# SBC_65C02_IRQ_BigBoard_v10-2-1.net
KiCad netlist of a schematic drawn in EAGLE
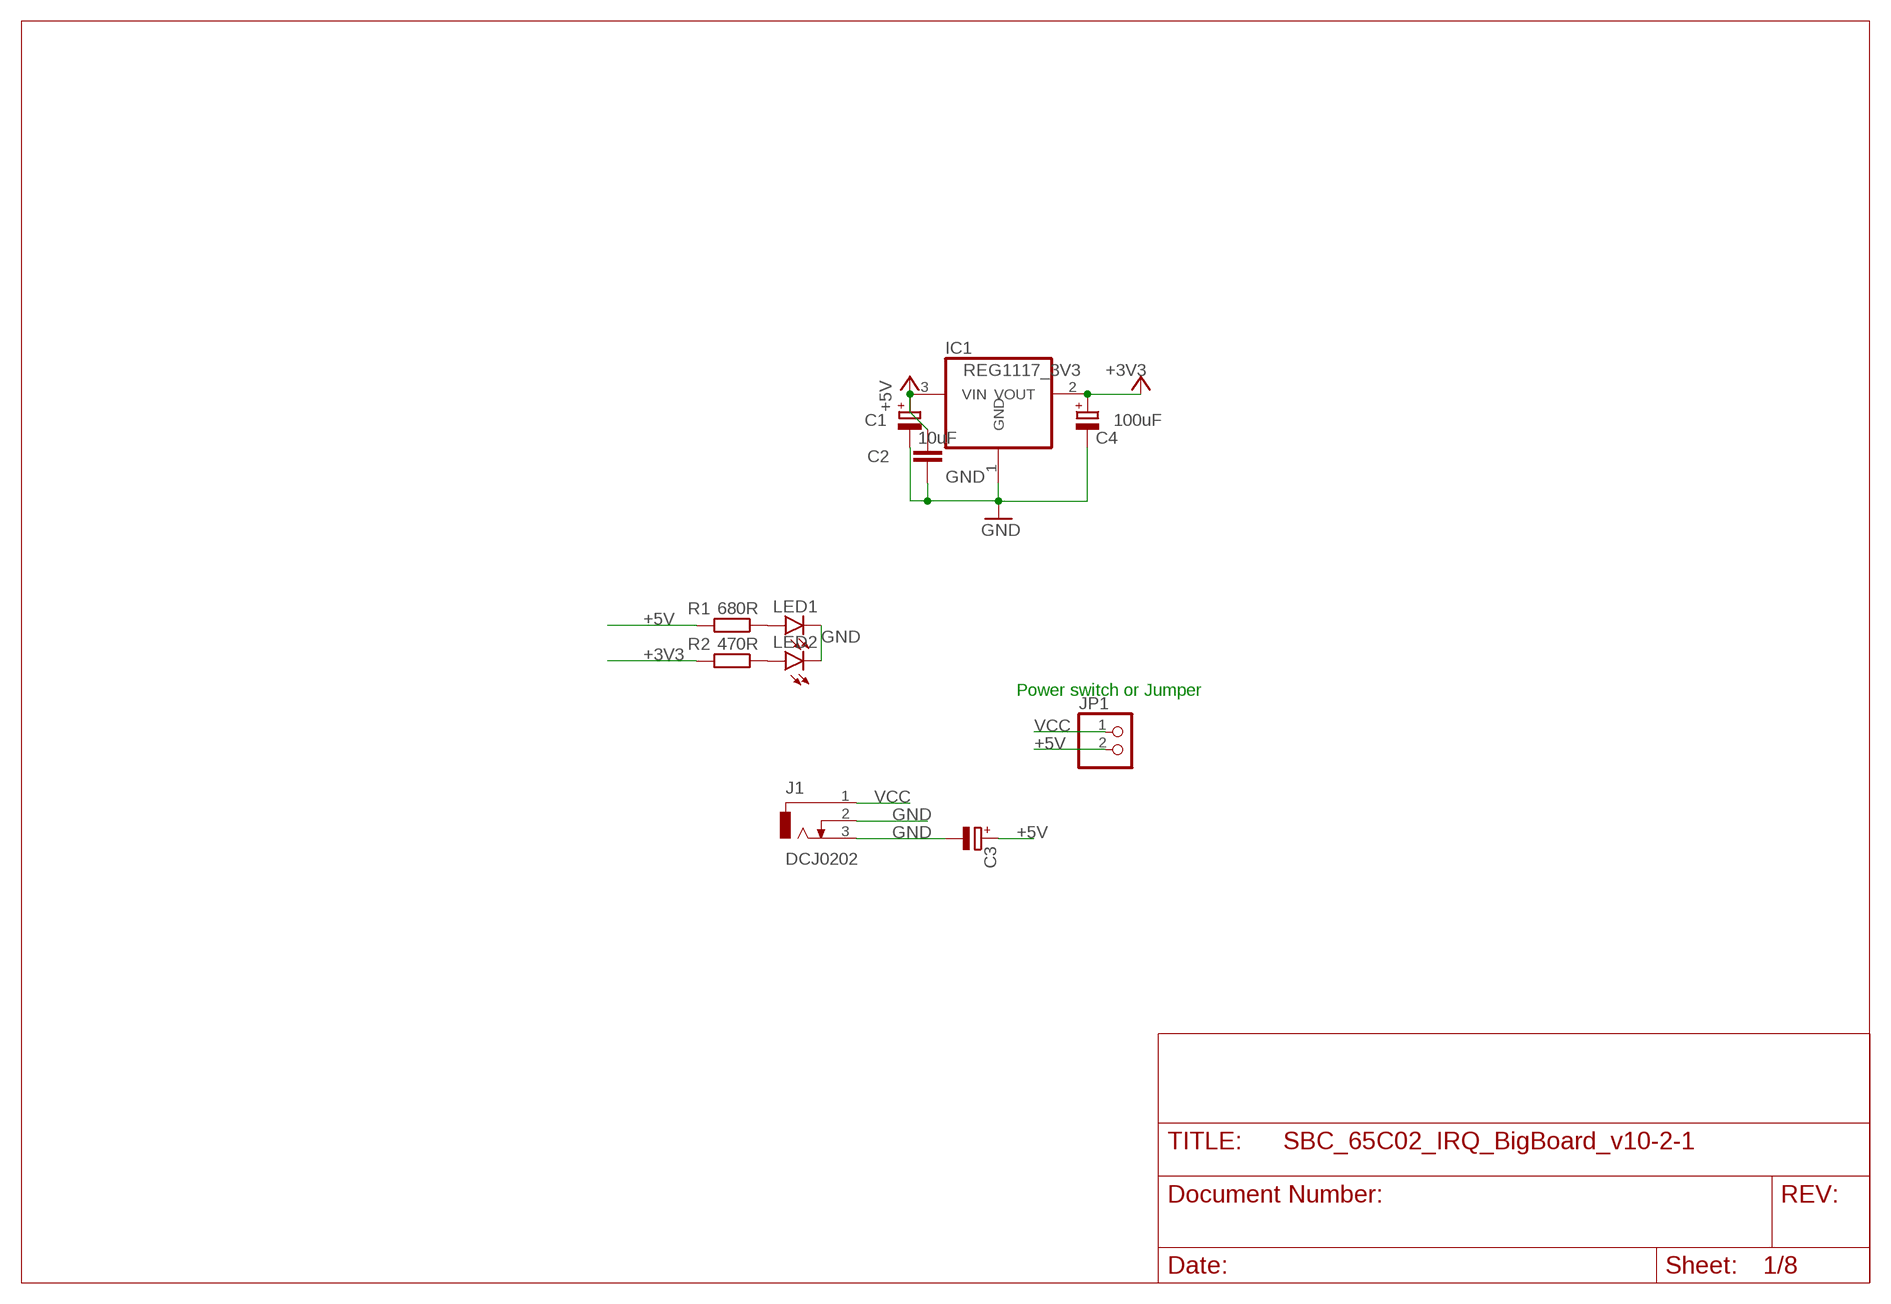
[diagram p0: schematic, sheet 1]
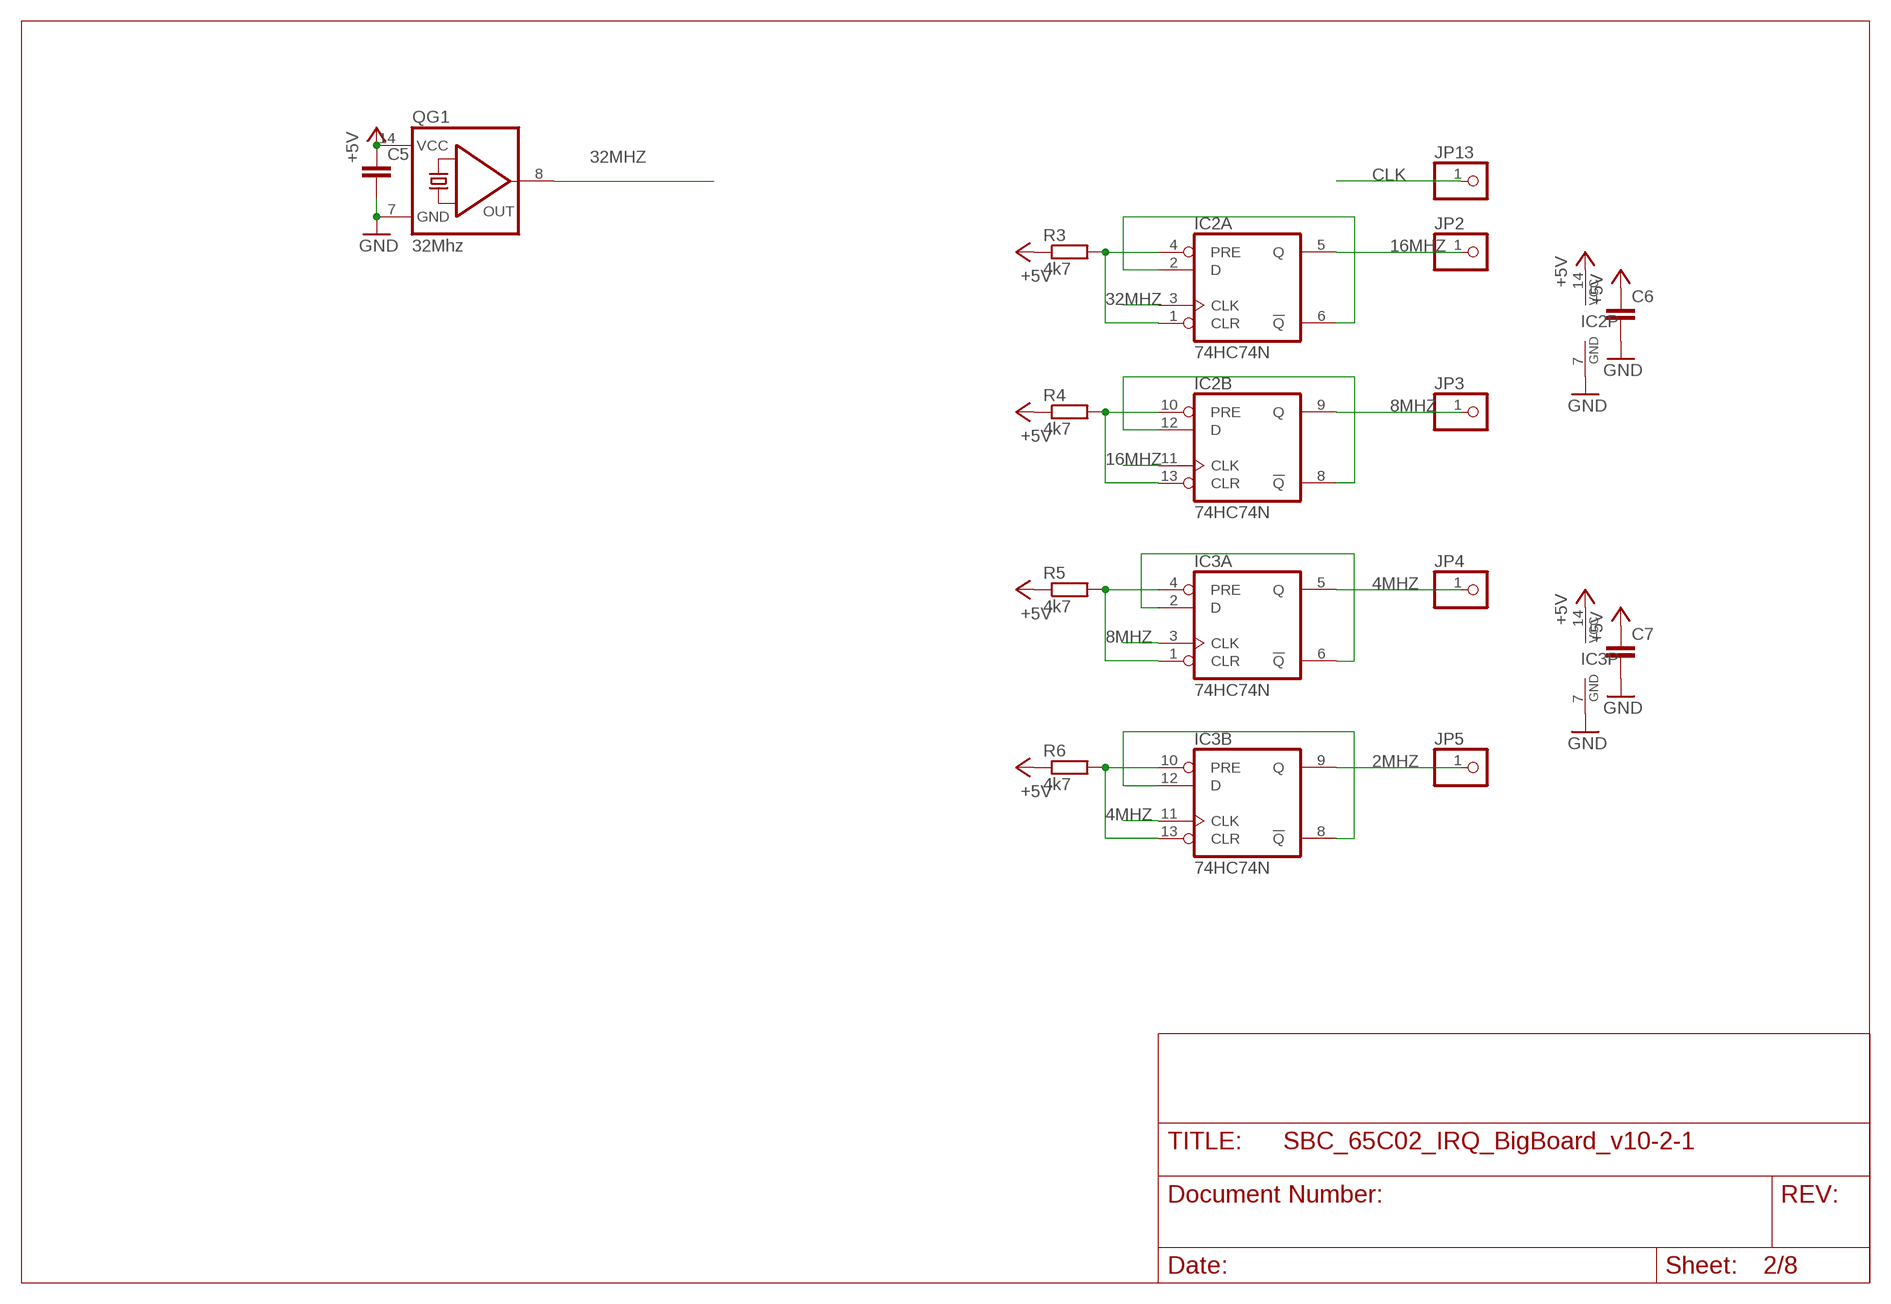
[diagram p1: schematic, sheet 2]
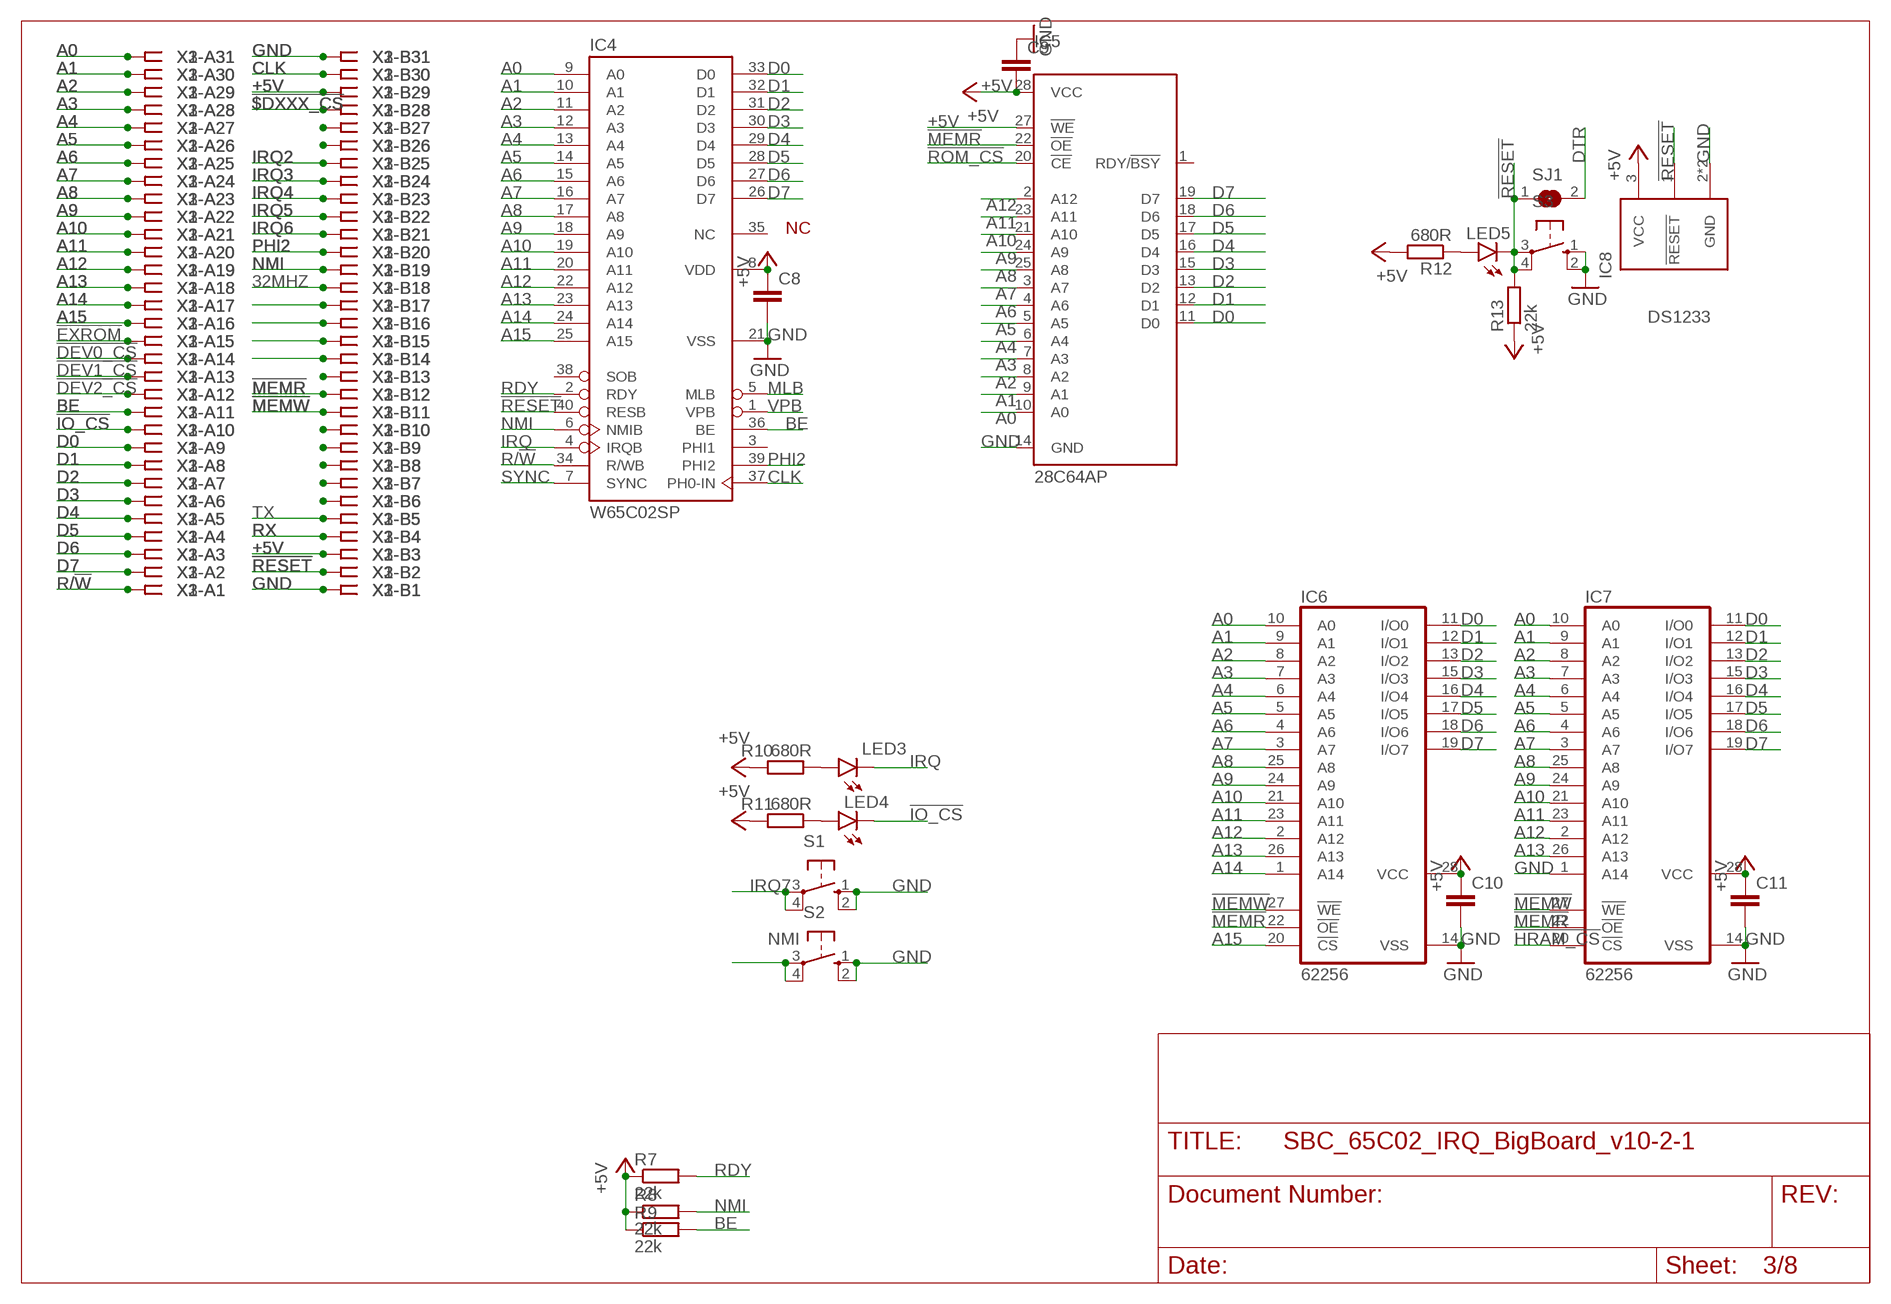
[diagram p2: schematic, sheet 3]
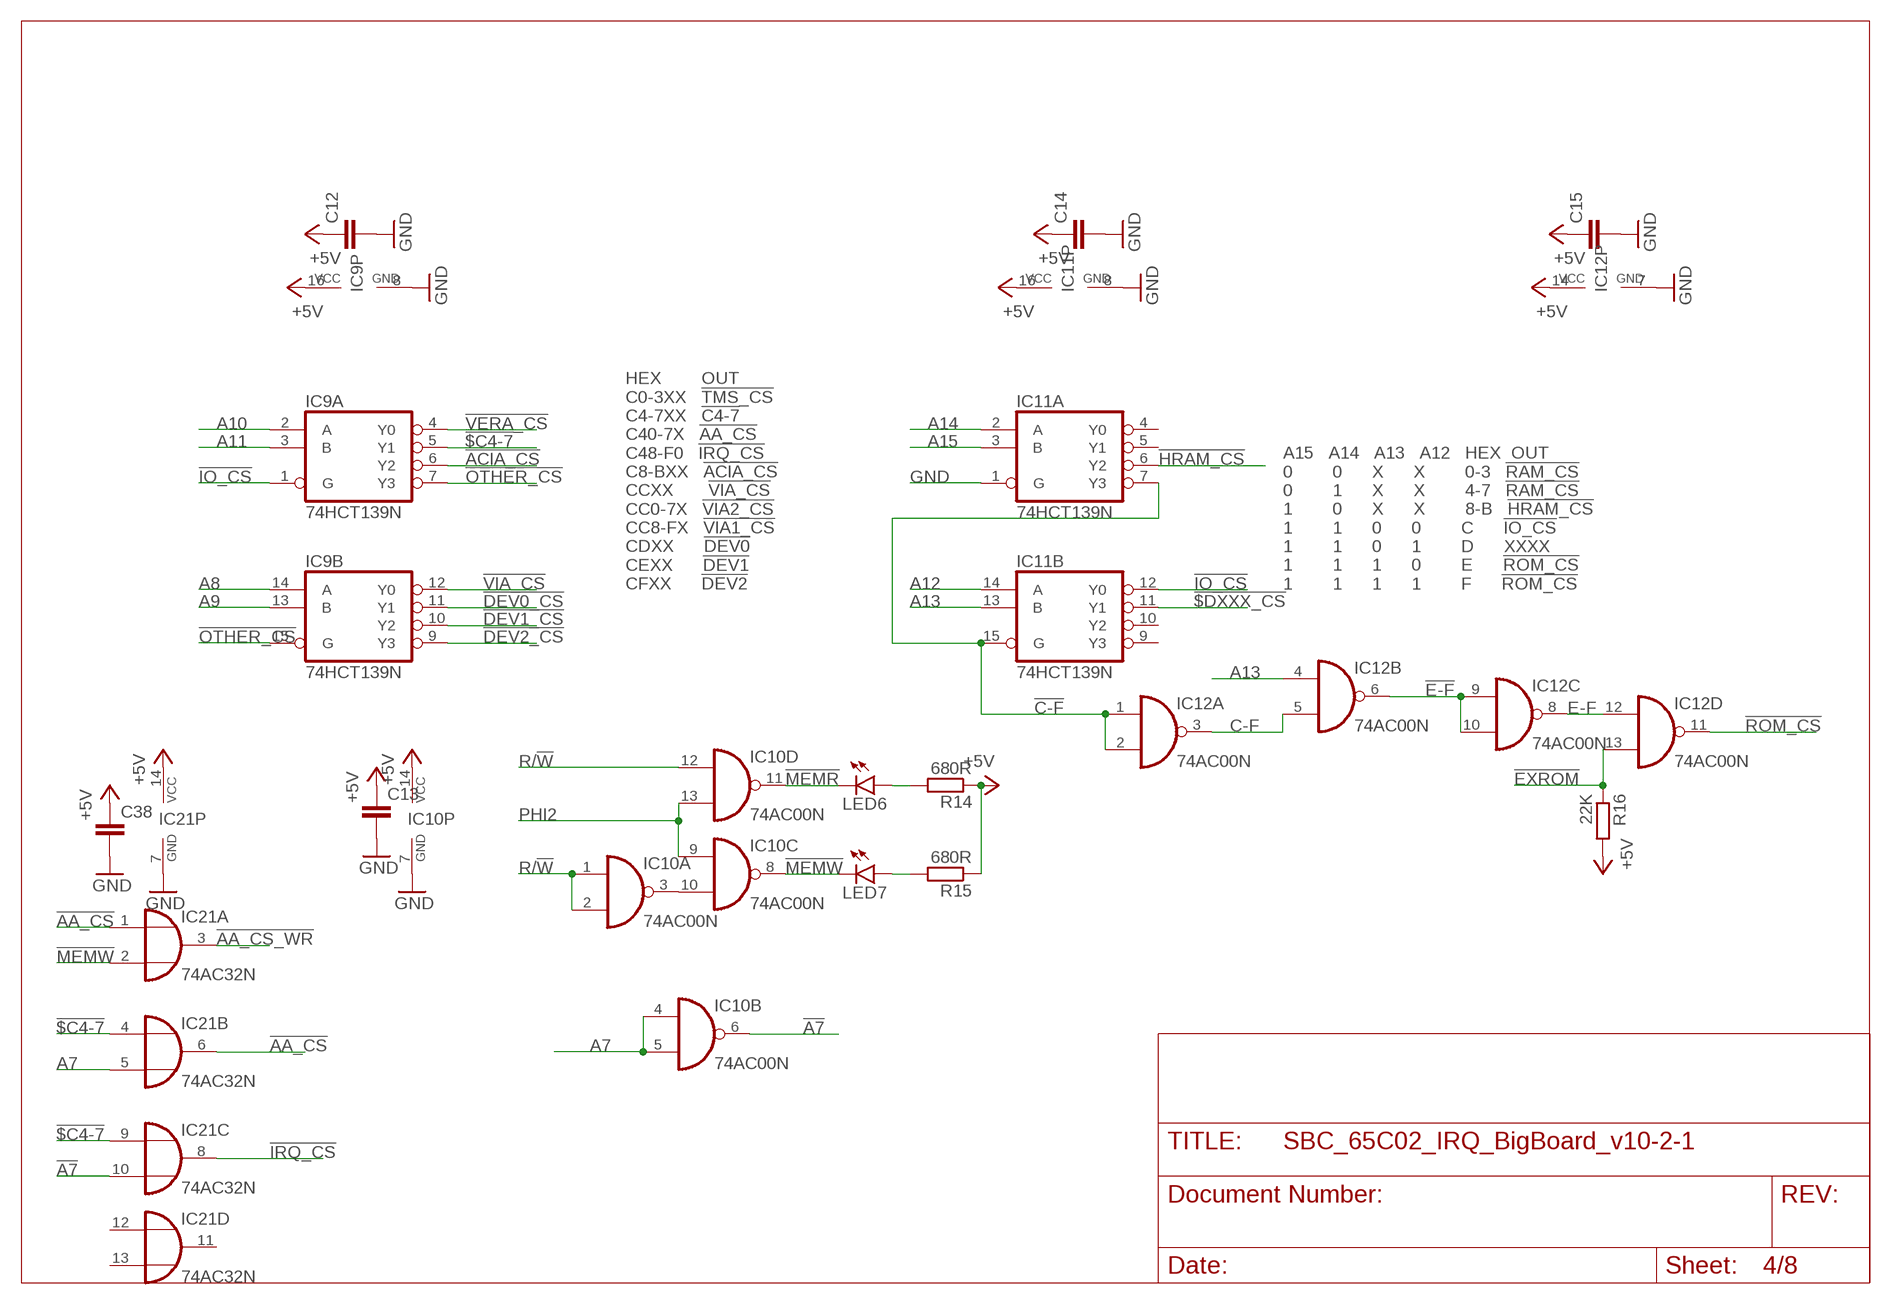
[diagram p3: schematic, sheet 4]
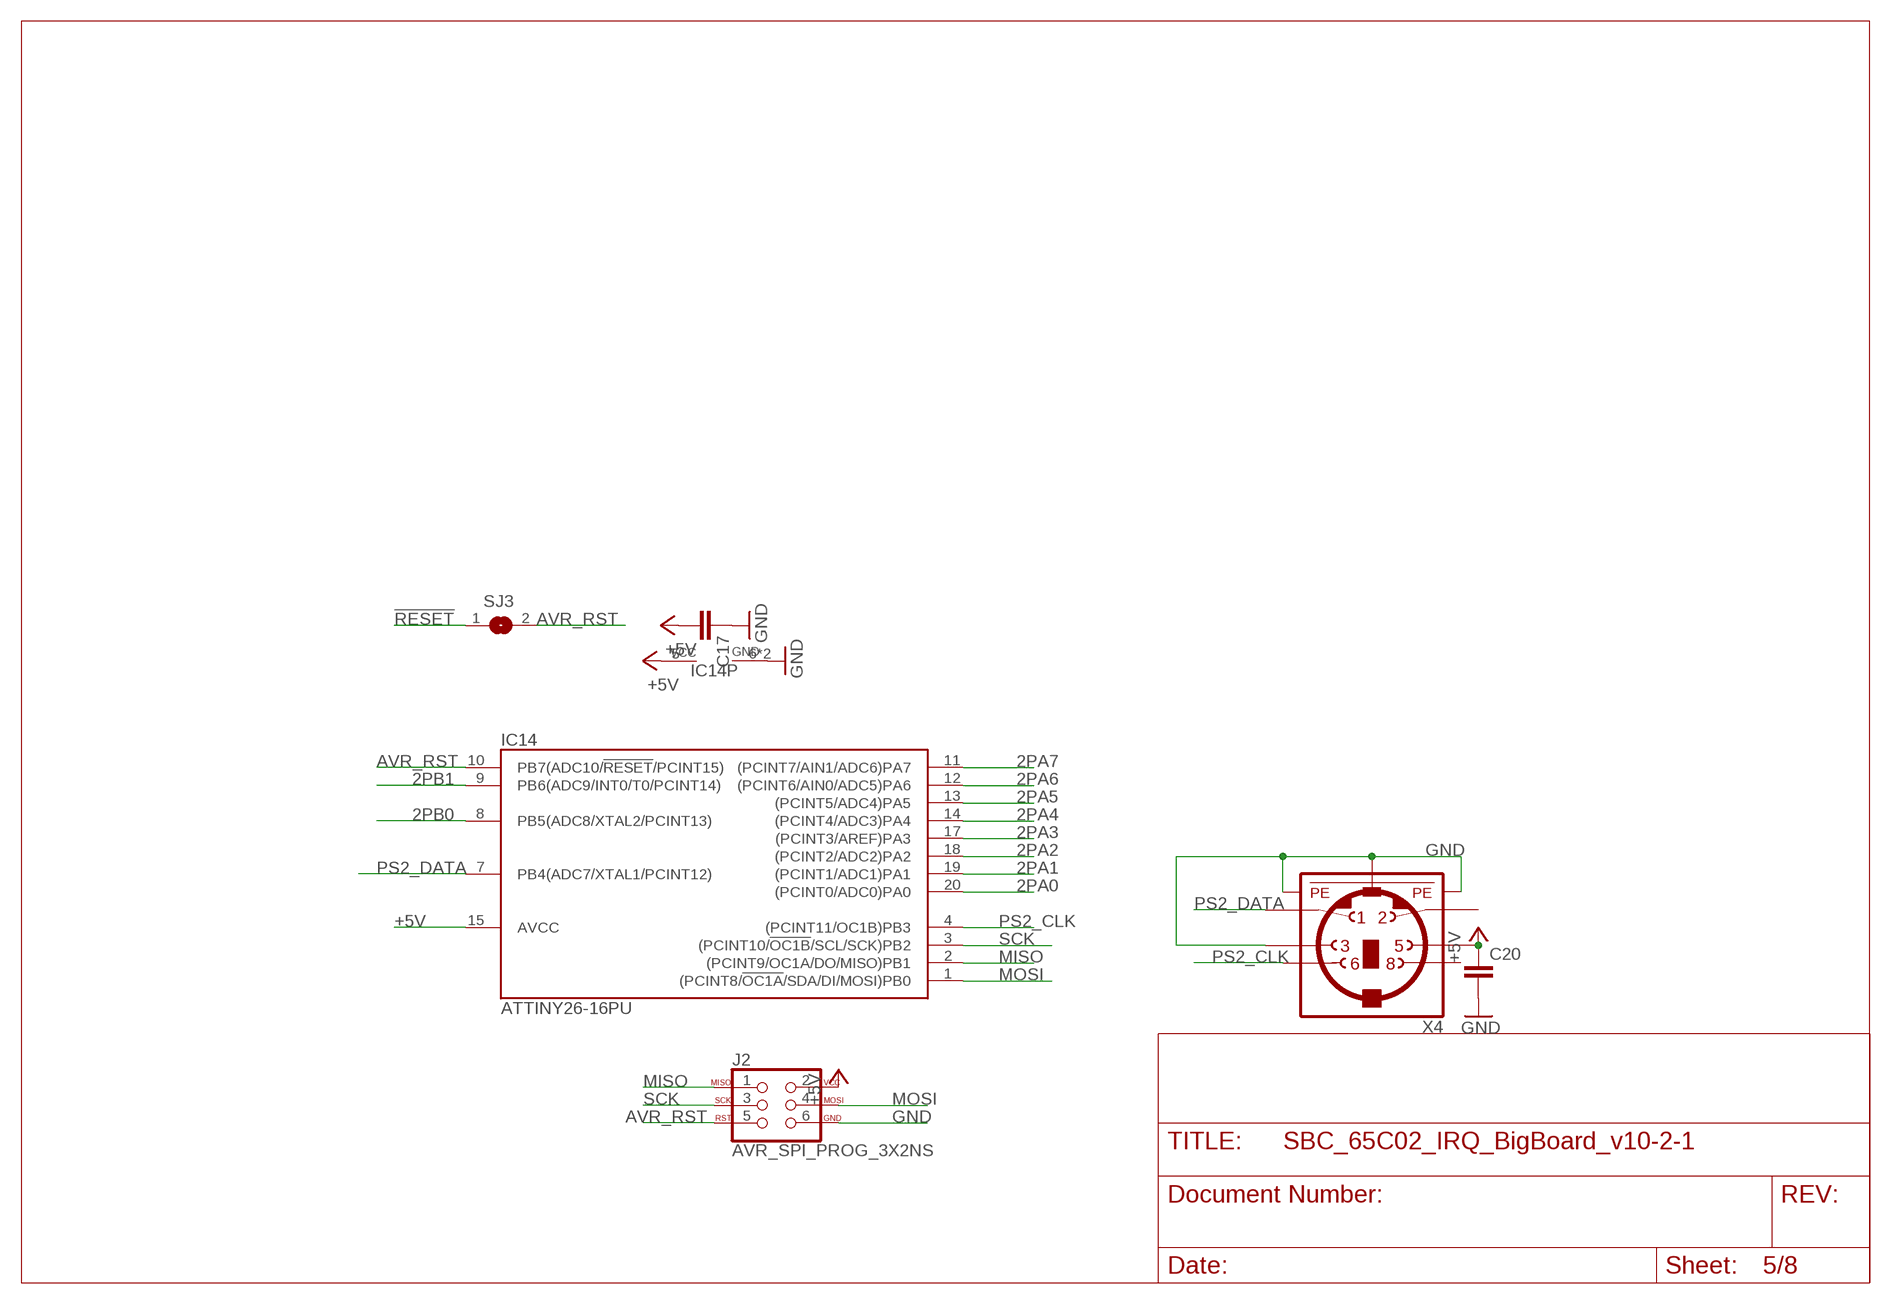
[diagram p4: schematic, sheet 5]
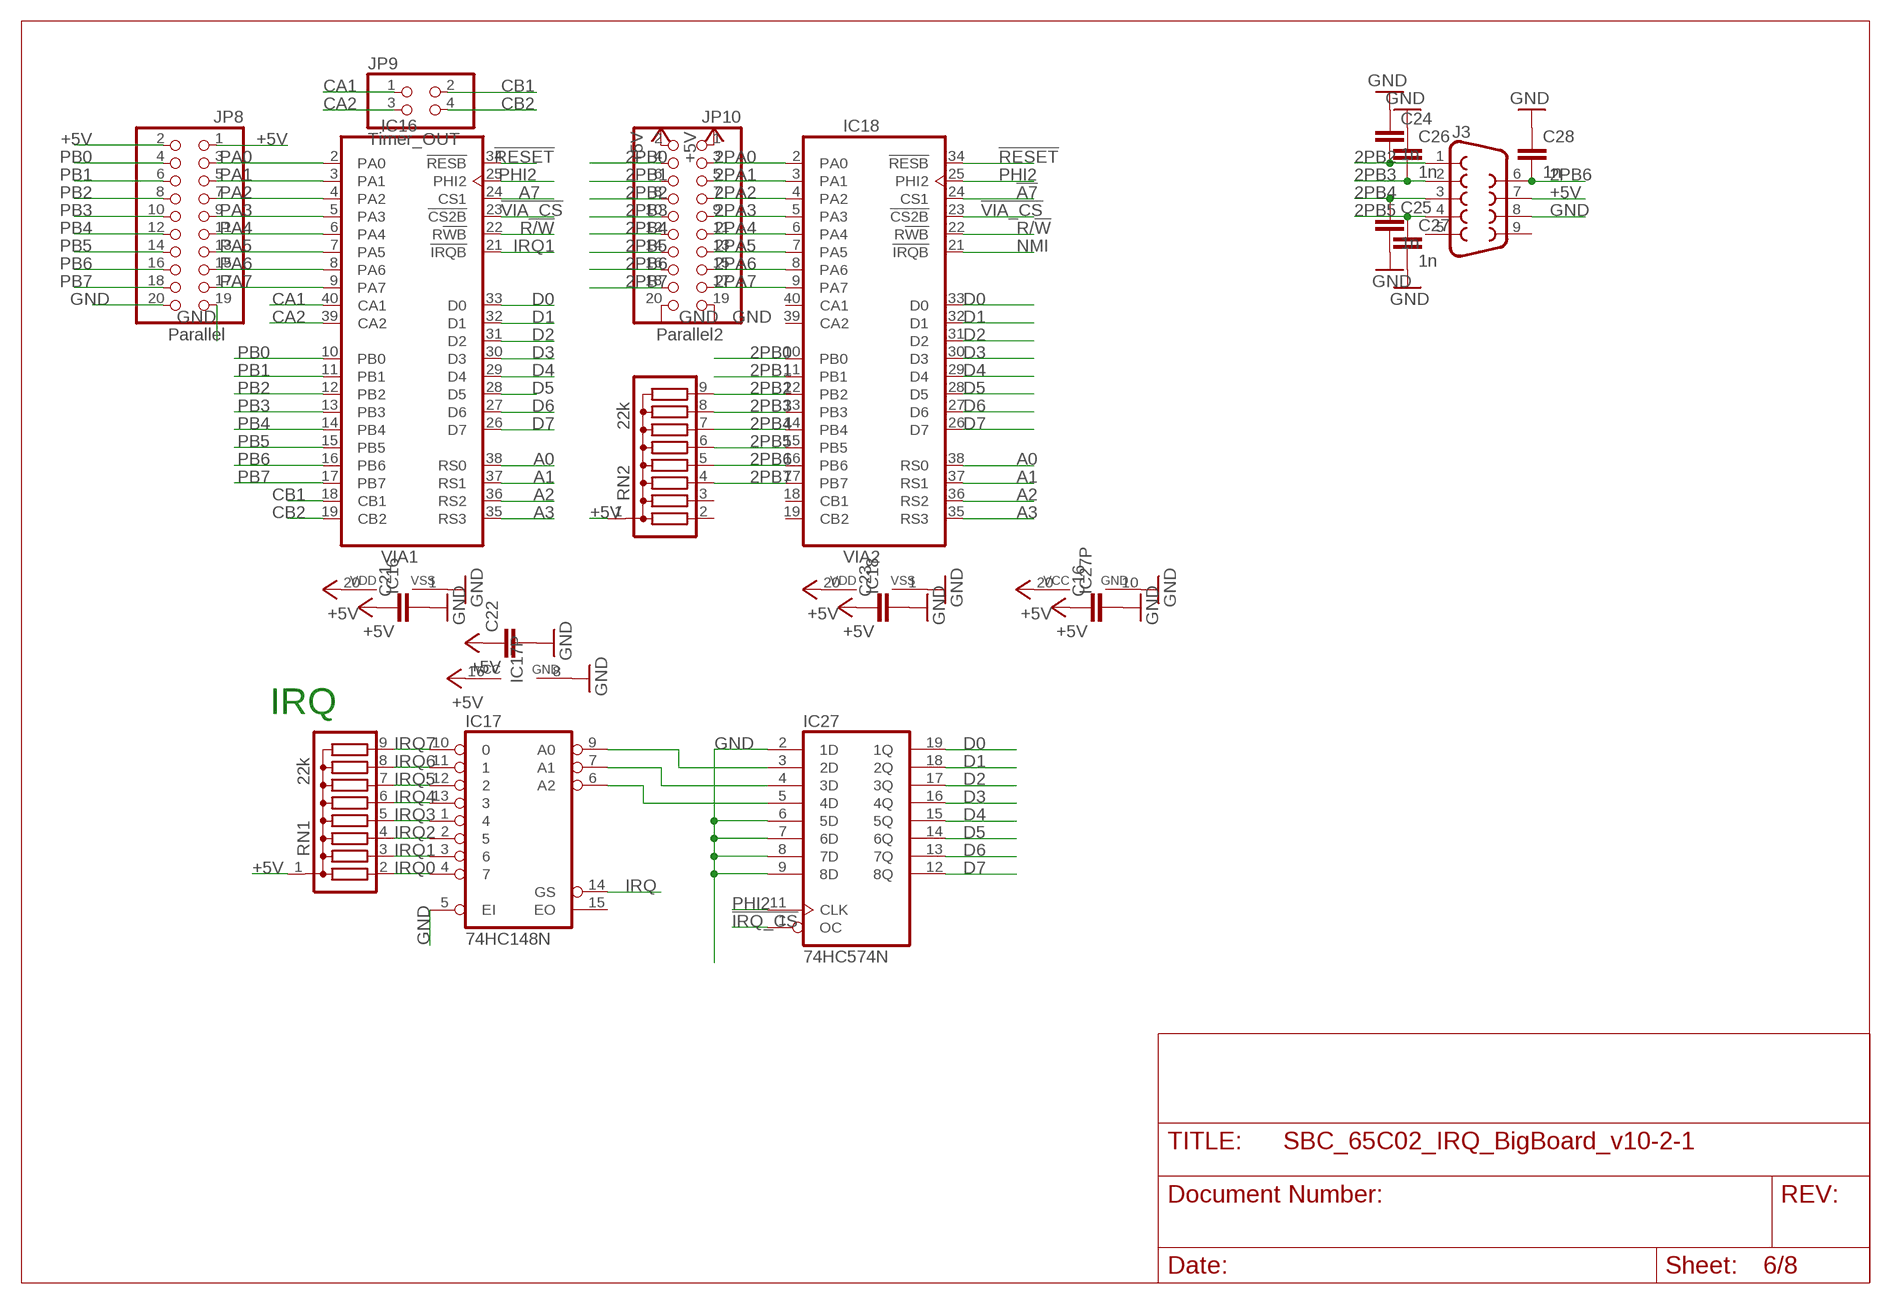
[diagram p5: schematic, sheet 6]
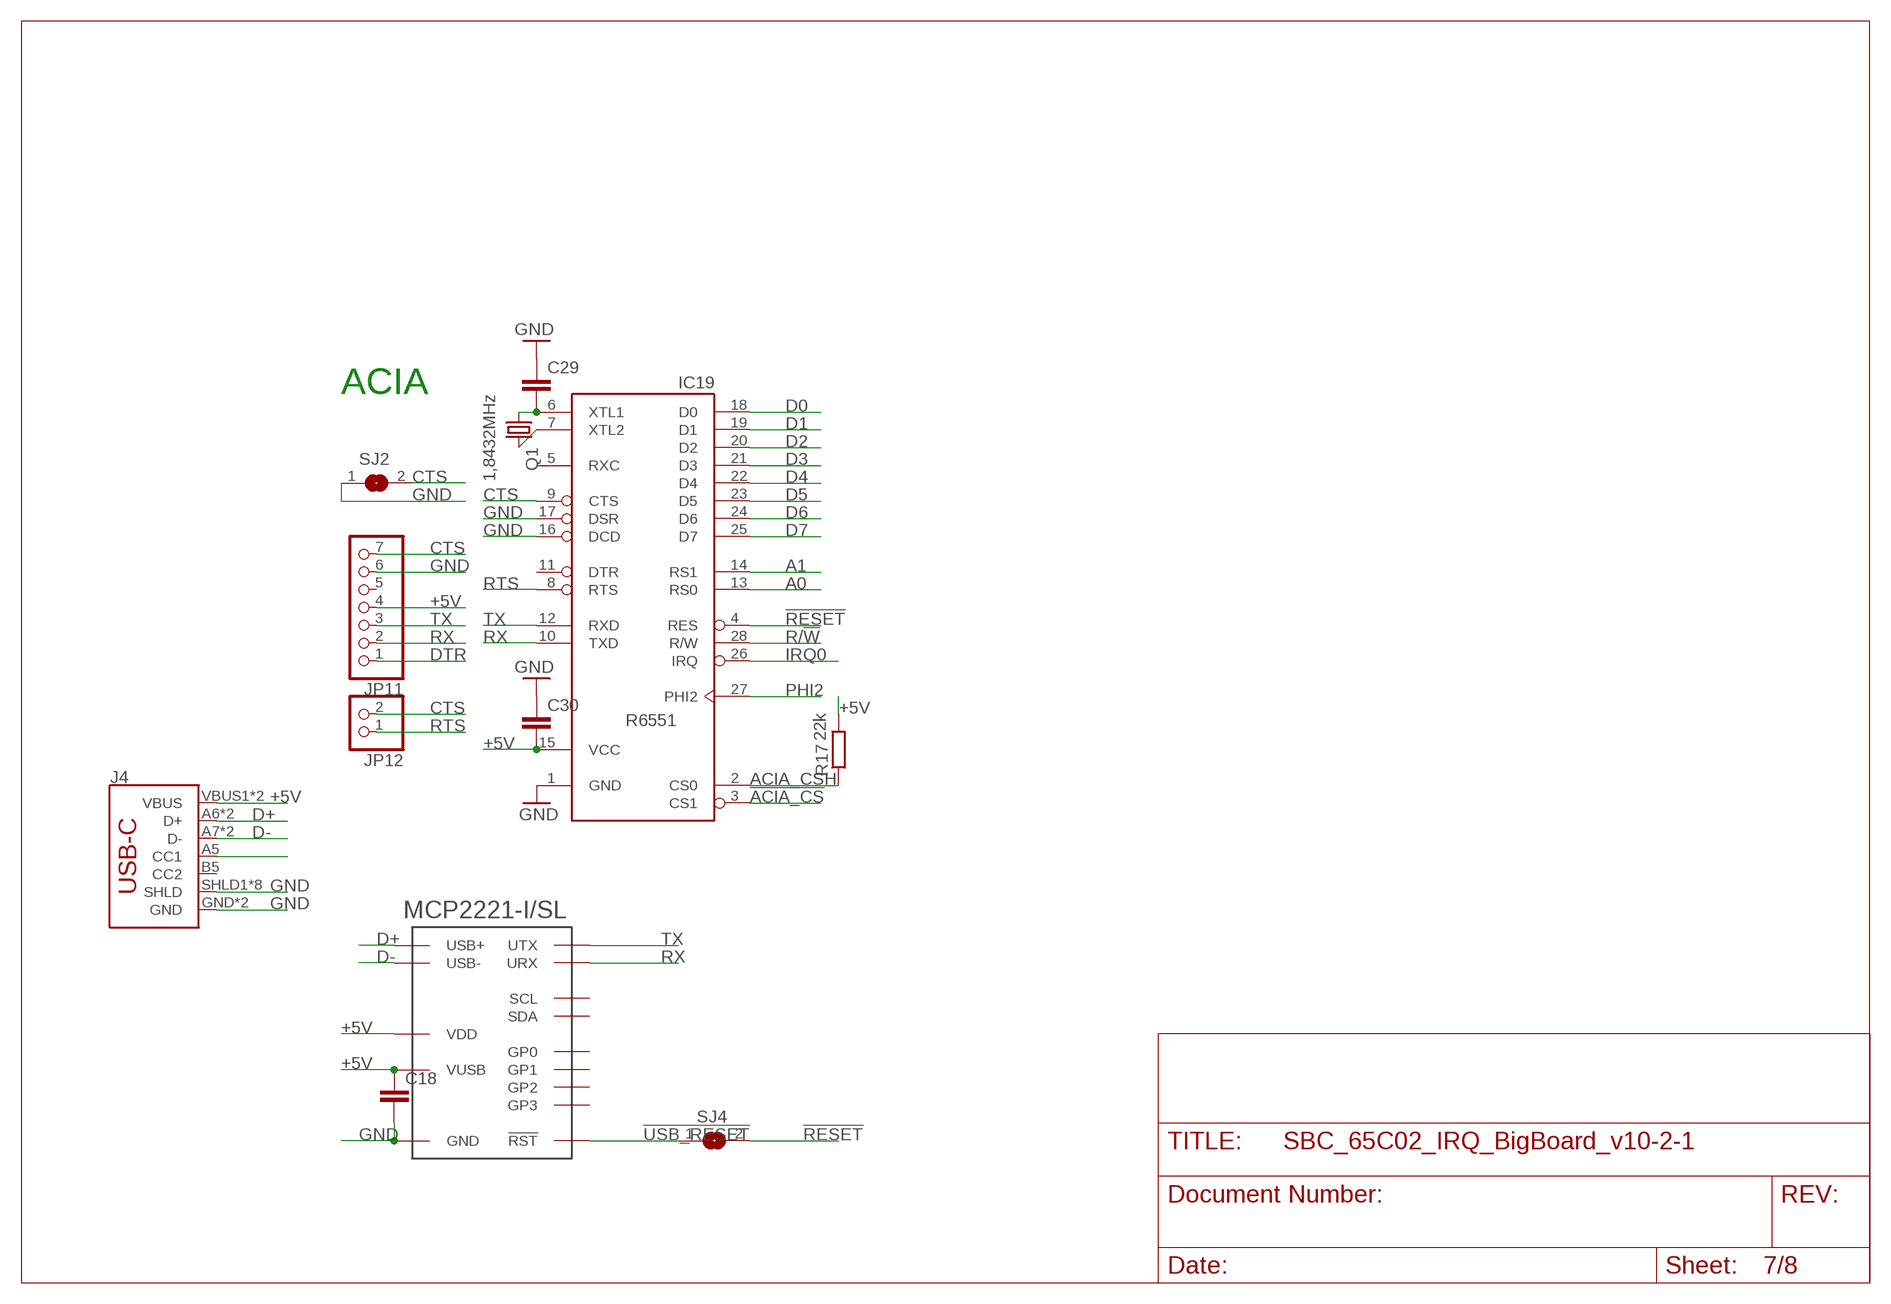
[diagram p6: schematic, sheet 7]
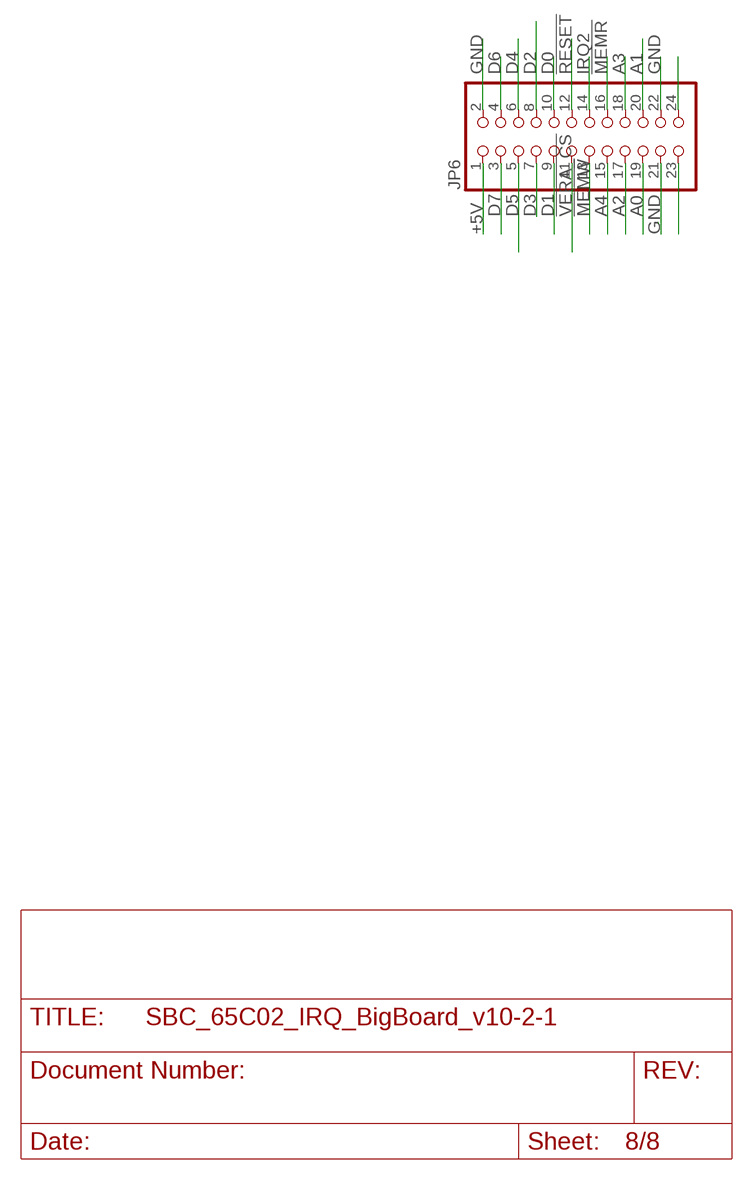
[diagram p7: schematic, sheet 8]

(export (version "E")
  (design (tool "Eeschema 10.0.6"))
  (components
    (comp (ref "JP6")
      (value "PINHD-2X12")
      (footprint "eagle-import:2X12")
      (libsource (lib "eagle-import") (part "PINHD-2X12"))
    )
    (comp (ref "C12")
      (value "C-EU050-025X075")
      (footprint "eagle-import:C050-025X075")
      (libsource (lib "eagle-import") (part "C-EU050-025X075"))
    )
    (comp (ref "C13")
      (value "C-EU050-025X075")
      (footprint "eagle-import:C050-025X075")
      (libsource (lib "eagle-import") (part "C-EU050-025X075"))
    )
    (comp (ref "C14")
      (value "C-EU050-025X075")
      (footprint "eagle-import:C050-025X075")
      (libsource (lib "eagle-import") (part "C-EU050-025X075"))
    )
    (comp (ref "C15")
      (value "C-EU050-025X075")
      (footprint "eagle-import:C050-025X075")
      (libsource (lib "eagle-import") (part "C-EU050-025X075"))
    )
    (comp (ref "C38")
      (value "C-EU050-025X075")
      (footprint "eagle-import:C050-025X075")
      (libsource (lib "eagle-import") (part "C-EU050-025X075"))
    )
    (comp (ref "IC9")
      (value "74HCT139N")
      (footprint "eagle-import:DIL16")
      (libsource (lib "eagle-import") (part "74139NHCT"))
    )
    (comp (ref "IC10")
      (value "74AC00N")
      (footprint "eagle-import:DIL14")
      (libsource (lib "eagle-import") (part "7400NAC"))
    )
    (comp (ref "IC11")
      (value "74HCT139N")
      (footprint "eagle-import:DIL16")
      (libsource (lib "eagle-import") (part "74139NHCT"))
    )
    (comp (ref "IC12")
      (value "74AC00N")
      (footprint "eagle-import:DIL14")
      (libsource (lib "eagle-import") (part "7400NAC"))
    )
    (comp (ref "IC21")
      (value "74AC32N")
      (footprint "eagle-import:DIL14")
      (libsource (lib "eagle-import") (part "7432NAC"))
    )
    (comp (ref "LED6")
      (value "LED5MM")
      (footprint "eagle-import:LED5MM")
      (libsource (lib "eagle-import") (part "LED5MM"))
    )
    (comp (ref "LED7")
      (value "LED5MM")
      (footprint "eagle-import:LED5MM")
      (libsource (lib "eagle-import") (part "LED5MM"))
    )
    (comp (ref "R14")
      (value "680R")
      (footprint "eagle-import:0207_10")
      (libsource (lib "eagle-import") (part "rcl_334_R-EU_0207/10"))
    )
    (comp (ref "R15")
      (value "680R")
      (footprint "eagle-import:0207_10")
      (libsource (lib "eagle-import") (part "rcl_334_R-EU_0207/10"))
    )
    (comp (ref "R16")
      (value "22K")
      (footprint "eagle-import:0207_10")
      (libsource (lib "eagle-import") (part "rcl_334_R-EU_0207/10"))
    )
    (comp (ref "C17")
      (value "C-EU050-025X075")
      (footprint "eagle-import:C050-025X075")
      (libsource (lib "eagle-import") (part "C-EU050-025X075"))
    )
    (comp (ref "C20")
      (value "C-EU050-025X075")
      (footprint "eagle-import:C050-025X075")
      (libsource (lib "eagle-import") (part "C-EU050-025X075"))
    )
    (comp (ref "IC14")
      (value "ATTINY26-16PU")
      (footprint "eagle-import:DIL20")
      (libsource (lib "eagle-import") (part "ATTINY26PU-16"))
    )
    (comp (ref "J2")
      (value "AVR_SPI_PROG_3X2NS")
      (footprint "eagle-import:2X3-NS")
      (libsource (lib "eagle-import") (part "AVR_SPI_PROG_3X2NS"))
    )
    (comp (ref "SJ3") (value "SJ") (footprint "eagle-import:SJ") (libsource (lib "eagle-import") (part "SJ")))
    (comp (ref "X4")
      (value "MINI_DIN_6")
      (footprint "eagle-import:M_DIN6")
      (libsource (lib "eagle-import") (part "MINI_DIN_6"))
    )
    (comp (ref "C18")
      (value "C-EU050-025X075")
      (footprint "eagle-import:C050-025X075")
      (libsource (lib "eagle-import") (part "C-EU050-025X075"))
    )
    (comp (ref "C29")
      (value "C-EU050-025X075")
      (footprint "eagle-import:C050-025X075")
      (libsource (lib "eagle-import") (part "C-EU050-025X075"))
    )
    (comp (ref "C30")
      (value "C-EU050-025X075")
      (footprint "eagle-import:C050-025X075")
      (libsource (lib "eagle-import") (part "C-EU050-025X075"))
    )
    (comp (ref "IC19")
      (value "R6551")
      (footprint "eagle-import:DIP-28")
      (libsource (lib "eagle-import") (part "R6551"))
    )
    (comp (ref "J4")
      (value "USB_C2-LAYER")
      (footprint "eagle-import:USB-C-16P")
      (libsource (lib "eagle-import") (part "USB_C2-LAYER"))
    )
    (comp (ref "JP11")
      (value "PINHD-1X7")
      (footprint "eagle-import:1X07")
      (libsource (lib "eagle-import") (part "PINHD-1X7"))
    )
    (comp (ref "JP12")
      (value "PINHD-1X2")
      (footprint "eagle-import:1X02")
      (libsource (lib "eagle-import") (part "PINHD-1X2"))
    )
    (comp (ref "Q1")
      (value "1,8432MHz")
      (footprint "eagle-import:HC49_S")
      (libsource (lib "eagle-import") (part "CRYSTALHC49S"))
    )
    (comp (ref "R17")
      (value "22k")
      (footprint "eagle-import:0207_10")
      (libsource (lib "eagle-import") (part "rcl_334_R-EU_0207/10"))
    )
    (comp (ref "SJ2") (value "SJ") (footprint "eagle-import:SJ") (libsource (lib "eagle-import") (part "SJ")))
    (comp (ref "SJ4") (value "SJ") (footprint "eagle-import:SJ") (libsource (lib "eagle-import") (part "SJ")))
    (comp (ref "U$1")
      (value "MCP2221A-I/P")
      (footprint "eagle-import:DIL14")
      (libsource (lib "eagle-import") (part "MCP2221A-I/P"))
    )
    (comp (ref "C16")
      (value "C-EU050-025X075")
      (footprint "eagle-import:C050-025X075")
      (libsource (lib "eagle-import") (part "C-EU050-025X075"))
    )
    (comp (ref "C21")
      (value "C-EU050-025X075")
      (footprint "eagle-import:C050-025X075")
      (libsource (lib "eagle-import") (part "C-EU050-025X075"))
    )
    (comp (ref "C22")
      (value "C-EU050-025X075")
      (footprint "eagle-import:C050-025X075")
      (libsource (lib "eagle-import") (part "C-EU050-025X075"))
    )
    (comp (ref "C23")
      (value "C-EU050-025X075")
      (footprint "eagle-import:C050-025X075")
      (libsource (lib "eagle-import") (part "C-EU050-025X075"))
    )
    (comp (ref "C24")
      (value "1n")
      (footprint "eagle-import:C050-025X075")
      (libsource (lib "eagle-import") (part "C-EU050-025X075"))
    )
    (comp (ref "C25")
      (value "1n")
      (footprint "eagle-import:C050-025X075")
      (libsource (lib "eagle-import") (part "C-EU050-025X075"))
    )
    (comp (ref "C26")
      (value "1n")
      (footprint "eagle-import:C050-025X075")
      (libsource (lib "eagle-import") (part "C-EU050-025X075"))
    )
    (comp (ref "C27")
      (value "1n")
      (footprint "eagle-import:C050-025X075")
      (libsource (lib "eagle-import") (part "C-EU050-025X075"))
    )
    (comp (ref "C28")
      (value "1n")
      (footprint "eagle-import:C050-025X075")
      (libsource (lib "eagle-import") (part "C-EU050-025X075"))
    )
    (comp (ref "IC16")
      (value "VIA1")
      (footprint "eagle-import:DIL40")
      (libsource (lib "eagle-import") (part "W65C22SP6T"))
    )
    (comp (ref "IC17")
      (value "74HC148N")
      (footprint "eagle-import:DIL16")
      (libsource (lib "eagle-import") (part "74148NHC"))
    )
    (comp (ref "IC18")
      (value "VIA2")
      (footprint "eagle-import:DIL40")
      (libsource (lib "eagle-import") (part "W65C22SP6T"))
    )
    (comp (ref "IC27")
      (value "74HC574N")
      (footprint "eagle-import:DIL20")
      (libsource (lib "eagle-import") (part "74574NHC"))
    )
    (comp (ref "J3")
      (value "DB9MALE")
      (footprint "eagle-import:DB9_MALE")
      (libsource (lib "eagle-import") (part "DB9MALE"))
    )
    (comp (ref "JP8")
      (value "Parallel")
      (footprint "eagle-import:2X10")
      (libsource (lib "eagle-import") (part "PINHD-2X10"))
    )
    (comp (ref "JP9")
      (value "Timer_OUT")
      (footprint "eagle-import:2X02")
      (libsource (lib "eagle-import") (part "PINHD-2X2"))
    )
    (comp (ref "JP10")
      (value "Parallel2")
      (footprint "eagle-import:2X10")
      (libsource (lib "eagle-import") (part "PINHD-2X10"))
    )
    (comp (ref "RN1")
      (value "22k")
      (footprint "eagle-import:SIL9")
      (libsource (lib "eagle-import") (part "G08R"))
    )
    (comp (ref "RN2")
      (value "22k")
      (footprint "eagle-import:SIL9")
      (libsource (lib "eagle-import") (part "G08R"))
    )
    (comp (ref "C1")
      (value "10uF")
      (footprint "eagle-import:E2,5-5")
      (libsource (lib "eagle-import") (part "CPOL-EUE2.5-5"))
    )
    (comp (ref "C2")
      (value "C-EU050-035X075")
      (footprint "eagle-import:C050-035X075")
      (libsource (lib "eagle-import") (part "C-EU050-035X075"))
    )
    (comp (ref "C3")
      (value "CPOL-EUE2.5-5")
      (footprint "eagle-import:E2,5-5")
      (libsource (lib "eagle-import") (part "CPOL-EUE2.5-5"))
    )
    (comp (ref "C4")
      (value "100uF")
      (footprint "eagle-import:E2,5-5")
      (libsource (lib "eagle-import") (part "CPOL-EUE2.5-5"))
    )
    (comp (ref "IC1")
      (value "REG1117_3V3")
      (footprint "eagle-import:SOT223")
      (fields (field (name "MPN") "REG1117"))
      (libsource (lib "eagle-import") (part "REG1117"))
    )
    (comp (ref "J1")
      (value "DCJ0202")
      (footprint "eagle-import:DCJ0202")
      (libsource (lib "eagle-import") (part "DCJ0202"))
    )
    (comp (ref "JP1")
      (value "PINHD-1X2")
      (footprint "eagle-import:1X02")
      (libsource (lib "eagle-import") (part "PINHD-1X2"))
    )
    (comp (ref "LED1")
      (value "LED5MM")
      (footprint "eagle-import:LED5MM")
      (libsource (lib "eagle-import") (part "LED5MM"))
    )
    (comp (ref "LED2")
      (value "LED5MM")
      (footprint "eagle-import:LED5MM")
      (libsource (lib "eagle-import") (part "LED5MM"))
    )
    (comp (ref "R1")
      (value "680R")
      (footprint "eagle-import:0207_10")
      (libsource (lib "eagle-import") (part "resistor_348_R-EU_0207/10"))
    )
    (comp (ref "R2")
      (value "470R")
      (footprint "eagle-import:0207_10")
      (libsource (lib "eagle-import") (part "resistor_348_R-EU_0207/10"))
    )
    (comp (ref "C8")
      (value "C-EU050-025X075")
      (footprint "eagle-import:C050-025X075")
      (libsource (lib "eagle-import") (part "C-EU050-025X075"))
    )
    (comp (ref "C9")
      (value "C-EU050-025X075")
      (footprint "eagle-import:C050-025X075")
      (libsource (lib "eagle-import") (part "C-EU050-025X075"))
    )
    (comp (ref "C10")
      (value "C-EU050-025X075")
      (footprint "eagle-import:C050-025X075")
      (libsource (lib "eagle-import") (part "C-EU050-025X075"))
    )
    (comp (ref "C11")
      (value "C-EU050-025X075")
      (footprint "eagle-import:C050-025X075")
      (libsource (lib "eagle-import") (part "C-EU050-025X075"))
    )
    (comp (ref "IC4")
      (value "W65C02SP")
      (footprint "eagle-import:DIL40")
      (libsource (lib "eagle-import") (part "W65C02SP"))
    )
    (comp (ref "IC5")
      (value "28C64AP")
      (footprint "eagle-import:DIL28-6")
      (fields (field (name "MPN") "AT28C64B-15PU"))
      (libsource (lib "eagle-import") (part "2864APC"))
    )
    (comp (ref "IC6")
      (value "62256")
      (footprint "eagle-import:DIL28-6")
      (libsource (lib "eagle-import") (part "62256P"))
    )
    (comp (ref "IC7")
      (value "62256")
      (footprint "eagle-import:DIL28-6")
      (libsource (lib "eagle-import") (part "62256P"))
    )
    (comp (ref "IC8")
      (value "DS1233")
      (footprint "eagle-import:SOT223")
      (libsource (lib "eagle-import") (part "DS1233SOT223"))
    )
    (comp (ref "LED3")
      (value "LED5MM")
      (footprint "eagle-import:LED5MM")
      (libsource (lib "eagle-import") (part "LED5MM"))
    )
    (comp (ref "LED4")
      (value "LED5MM")
      (footprint "eagle-import:LED5MM")
      (libsource (lib "eagle-import") (part "LED5MM"))
    )
    (comp (ref "LED5")
      (value "LED5MM")
      (footprint "eagle-import:LED5MM")
      (libsource (lib "eagle-import") (part "LED5MM"))
    )
    (comp (ref "R7")
      (value "22k")
      (footprint "eagle-import:0207_10")
      (libsource (lib "eagle-import") (part "R-EU_0207/10"))
    )
    (comp (ref "R8")
      (value "22k")
      (footprint "eagle-import:0207_10")
      (libsource (lib "eagle-import") (part "R-EU_0207/10"))
    )
    (comp (ref "R9")
      (value "22k")
      (footprint "eagle-import:0207_10")
      (libsource (lib "eagle-import") (part "R-EU_0207/10"))
    )
    (comp (ref "R10")
      (value "680R")
      (footprint "eagle-import:0207_10")
      (libsource (lib "eagle-import") (part "resistor_348_R-EU_0207/10"))
    )
    (comp (ref "R11")
      (value "680R")
      (footprint "eagle-import:0207_10")
      (libsource (lib "eagle-import") (part "resistor_348_R-EU_0207/10"))
    )
    (comp (ref "R12")
      (value "680R")
      (footprint "eagle-import:0207_10")
      (libsource (lib "eagle-import") (part "resistor_348_R-EU_0207/10"))
    )
    (comp (ref "R13")
      (value "22k")
      (footprint "eagle-import:0207_10")
      (libsource (lib "eagle-import") (part "resistor_348_R-EU_0207/10"))
    )
    (comp (ref "S1")
      (value "10-XX")
      (footprint "eagle-import:B3F-10XX")
      (fields (field (name "MPN") "B3F-1000"))
      (libsource (lib "eagle-import") (part "10-XX"))
    )
    (comp (ref "S2")
      (value "10-XX")
      (footprint "eagle-import:B3F-10XX")
      (fields (field (name "MPN") "B3F-1000"))
      (libsource (lib "eagle-import") (part "10-XX"))
    )
    (comp (ref "S3")
      (value "10-XX")
      (footprint "eagle-import:B3F-10XX")
      (fields (field (name "MPN") "B3F-1000"))
      (libsource (lib "eagle-import") (part "10-XX"))
    )
    (comp (ref "SJ1") (value "SJ") (footprint "eagle-import:SJ") (libsource (lib "eagle-import") (part "SJ")))
    (comp (ref "X1")
      (value "ISA-SLOT")
      (footprint "eagle-import:ISA-8")
      (libsource (lib "eagle-import") (part "ISA-SLOT"))
    )
    (comp (ref "X2")
      (value "ISA-SLOT")
      (footprint "eagle-import:ISA-8")
      (libsource (lib "eagle-import") (part "ISA-SLOT"))
    )
    (comp (ref "X3")
      (value "ISA-SLOT")
      (footprint "eagle-import:ISA-8")
      (libsource (lib "eagle-import") (part "ISA-SLOT"))
    )
    (comp (ref "C5")
      (value "C-EU050-025X075")
      (footprint "eagle-import:C050-025X075")
      (libsource (lib "eagle-import") (part "C-EU050-025X075"))
    )
    (comp (ref "C6")
      (value "C-EU050-025X075")
      (footprint "eagle-import:C050-025X075")
      (libsource (lib "eagle-import") (part "C-EU050-025X075"))
    )
    (comp (ref "C7")
      (value "C-EU050-025X075")
      (footprint "eagle-import:C050-025X075")
      (libsource (lib "eagle-import") (part "C-EU050-025X075"))
    )
    (comp (ref "IC2")
      (value "74HC74N")
      (footprint "eagle-import:DIL14")
      (libsource (lib "eagle-import") (part "7474NHC"))
    )
    (comp (ref "IC3")
      (value "74HC74N")
      (footprint "eagle-import:DIL14")
      (libsource (lib "eagle-import") (part "7474NHC"))
    )
    (comp (ref "JP2")
      (value "PINHD-1X1")
      (footprint "eagle-import:1X01")
      (libsource (lib "eagle-import") (part "PINHD-1X1"))
    )
    (comp (ref "JP3")
      (value "PINHD-1X1")
      (footprint "eagle-import:1X01")
      (libsource (lib "eagle-import") (part "PINHD-1X1"))
    )
    (comp (ref "JP4")
      (value "PINHD-1X1")
      (footprint "eagle-import:1X01")
      (libsource (lib "eagle-import") (part "PINHD-1X1"))
    )
    (comp (ref "JP5")
      (value "PINHD-1X1")
      (footprint "eagle-import:1X01")
      (libsource (lib "eagle-import") (part "PINHD-1X1"))
    )
    (comp (ref "JP13")
      (value "PINHD-1X1")
      (footprint "eagle-import:1X01")
      (libsource (lib "eagle-import") (part "PINHD-1X1"))
    )
    (comp (ref "QG1")
      (value "32Mhz")
      (footprint "eagle-import:DIL14S")
      (libsource (lib "eagle-import") (part "QG5860"))
    )
    (comp (ref "R3")
      (value "4k7")
      (footprint "eagle-import:0204_7")
      (libsource (lib "eagle-import") (part "rcl_334_R-EU_0204/7"))
    )
    (comp (ref "R4")
      (value "4k7")
      (footprint "eagle-import:0204_7")
      (libsource (lib "eagle-import") (part "rcl_334_R-EU_0204/7"))
    )
    (comp (ref "R5")
      (value "4k7")
      (footprint "eagle-import:0204_7")
      (libsource (lib "eagle-import") (part "rcl_334_R-EU_0204/7"))
    )
    (comp (ref "R6")
      (value "4k7")
      (footprint "eagle-import:0204_7")
      (libsource (lib "eagle-import") (part "rcl_334_R-EU_0204/7"))
    )
  )
  (nets
    (net (code "1") (name "+3V3") (class "Default")
      (node (ref "C4") (pin "+") (pinfunction "+_+") (pintype "passive"))
      (node (ref "IC1") (pin "2") (pinfunction "VOUT_2") (pintype "output"))
      (node (ref "R2") (pin "2") (pinfunction "2_2") (pintype "passive"))
    )
    (net (code "2") (name "+5V") (class "Default")
      (node (ref "C1") (pin "+") (pinfunction "+_+") (pintype "passive"))
      (node (ref "C10") (pin "1") (pinfunction "1_1") (pintype "passive"))
      (node (ref "C11") (pin "1") (pinfunction "1_1") (pintype "passive"))
      (node (ref "C12") (pin "1") (pinfunction "1_1") (pintype "passive"))
      (node (ref "C13") (pin "1") (pinfunction "1_1") (pintype "passive"))
      (node (ref "C14") (pin "1") (pinfunction "1_1") (pintype "passive"))
      (node (ref "C15") (pin "1") (pinfunction "1_1") (pintype "passive"))
      (node (ref "C16") (pin "1") (pinfunction "1_1") (pintype "passive"))
      (node (ref "C17") (pin "2") (pinfunction "2_2") (pintype "passive"))
      (node (ref "C18") (pin "1") (pinfunction "1_1") (pintype "passive"))
      (node (ref "C2") (pin "1") (pinfunction "1_1") (pintype "passive"))
      (node (ref "C20") (pin "1") (pinfunction "1_1") (pintype "passive"))
      (node (ref "C21") (pin "1") (pinfunction "1_1") (pintype "passive"))
      (node (ref "C22") (pin "1") (pinfunction "1_1") (pintype "passive"))
      (node (ref "C23") (pin "1") (pinfunction "1_1") (pintype "passive"))
      (node (ref "C3") (pin "+") (pinfunction "+_+") (pintype "passive"))
      (node (ref "C30") (pin "2") (pinfunction "2_2") (pintype "passive"))
      (node (ref "C38") (pin "1") (pinfunction "1_1") (pintype "passive"))
      (node (ref "C5") (pin "1") (pinfunction "1_1") (pintype "passive"))
      (node (ref "C6") (pin "1") (pinfunction "1_1") (pintype "passive"))
      (node (ref "C7") (pin "1") (pinfunction "1_1") (pintype "passive"))
      (node (ref "C8") (pin "1") (pinfunction "1_1") (pintype "passive"))
      (node (ref "C9") (pin "2") (pinfunction "2_2") (pintype "passive"))
      (node (ref "IC1") (pin "3") (pinfunction "VIN_3") (pintype "input"))
      (node (ref "IC10") (pin "14") (pinfunction "VCC_14") (pintype "power_in"))
      (node (ref "IC11") (pin "16") (pinfunction "VCC_16") (pintype "power_in"))
      (node (ref "IC12") (pin "14") (pinfunction "VCC_14") (pintype "power_in"))
      (node (ref "IC14") (pin "15") (pinfunction "AVCC_15") (pintype "power_in"))
      (node (ref "IC14") (pin "5") (pinfunction "VCC_5") (pintype "power_in"))
      (node (ref "IC16") (pin "20") (pinfunction "VDD_20") (pintype "power_in"))
      (node (ref "IC17") (pin "16") (pinfunction "VCC_16") (pintype "power_in"))
      (node (ref "IC18") (pin "20") (pinfunction "VDD_20") (pintype "power_in"))
      (node (ref "IC19") (pin "15") (pinfunction "VCC_15") (pintype "power_in"))
      (node (ref "IC2") (pin "14") (pinfunction "VCC_14") (pintype "power_in"))
      (node (ref "IC21") (pin "14") (pinfunction "VCC_14") (pintype "power_in"))
      (node (ref "IC27") (pin "20") (pinfunction "VCC_20") (pintype "power_in"))
      (node (ref "IC3") (pin "14") (pinfunction "VCC_14") (pintype "power_in"))
      (node (ref "IC4") (pin "8") (pinfunction "VDD_8") (pintype "power_in"))
      (node (ref "IC5") (pin "27") (pinfunction "~{WE}_27") (pintype "input"))
      (node (ref "IC5") (pin "28") (pinfunction "VCC_28") (pintype "power_in"))
      (node (ref "IC6") (pin "28") (pinfunction "VCC_28") (pintype "power_in"))
      (node (ref "IC7") (pin "28") (pinfunction "VCC_28") (pintype "power_in"))
      (node (ref "IC8") (pin "3") (pinfunction "VCC_3") (pintype "bidirectional"))
      (node (ref "IC9") (pin "16") (pinfunction "VCC_16") (pintype "power_in"))
      (node (ref "J2") (pin "2") (pinfunction "2_2") (pintype "passive"))
      (node (ref "J3") (pin "7") (pinfunction "7_7") (pintype "passive"))
      (node (ref "J4") (pin "VBUS1") (pinfunction "VBUS_VBUS1") (pintype "bidirectional"))
      (node (ref "J4") (pin "VBUS2") (pinfunction "VBUS_VBUS2") (pintype "bidirectional"))
      (node (ref "JP1") (pin "2") (pinfunction "2_2") (pintype "passive"))
      (node (ref "JP10") (pin "1") (pinfunction "1_1") (pintype "passive"))
      (node (ref "JP10") (pin "2") (pinfunction "2_2") (pintype "passive"))
      (node (ref "JP11") (pin "4") (pinfunction "4_4") (pintype "passive"))
      (node (ref "JP6") (pin "1") (pinfunction "1_1") (pintype "passive"))
      (node (ref "JP8") (pin "1") (pinfunction "1_1") (pintype "passive"))
      (node (ref "JP8") (pin "2") (pinfunction "2_2") (pintype "passive"))
      (node (ref "QG1") (pin "14") (pinfunction "VCC_14") (pintype "power_in"))
      (node (ref "R1") (pin "2") (pinfunction "2_2") (pintype "passive"))
      (node (ref "R10") (pin "2") (pinfunction "2_2") (pintype "passive"))
      (node (ref "R11") (pin "2") (pinfunction "2_2") (pintype "passive"))
      (node (ref "R12") (pin "2") (pinfunction "2_2") (pintype "passive"))
      (node (ref "R13") (pin "1") (pinfunction "1_1") (pintype "passive"))
      (node (ref "R14") (pin "1") (pinfunction "1_1") (pintype "passive"))
      (node (ref "R15") (pin "1") (pinfunction "1_1") (pintype "passive"))
      (node (ref "R16") (pin "2") (pinfunction "2_2") (pintype "passive"))
      (node (ref "R17") (pin "2") (pinfunction "2_2") (pintype "passive"))
      (node (ref "R3") (pin "1") (pinfunction "1_1") (pintype "passive"))
      (node (ref "R4") (pin "1") (pinfunction "1_1") (pintype "passive"))
      (node (ref "R5") (pin "1") (pinfunction "1_1") (pintype "passive"))
      (node (ref "R6") (pin "1") (pinfunction "1_1") (pintype "passive"))
      (node (ref "R7") (pin "1") (pinfunction "1_1") (pintype "passive"))
      (node (ref "R8") (pin "1") (pinfunction "1_1") (pintype "passive"))
      (node (ref "R9") (pin "1") (pinfunction "1_1") (pintype "passive"))
      (node (ref "RN1") (pin "1") (pinfunction "1_1") (pintype "passive"))
      (node (ref "RN2") (pin "1") (pinfunction "1_1") (pintype "passive"))
      (node (ref "U$1") (pin "1") (pinfunction "VDD_1") (pintype "bidirectional"))
      (node (ref "U$1") (pin "11") (pinfunction "VUSB_11") (pintype "bidirectional"))
      (node (ref "X1") (pin "B29") (pinfunction "P_B29") (pintype "passive"))
      (node (ref "X1") (pin "B3") (pinfunction "P_B3") (pintype "passive"))
      (node (ref "X2") (pin "B29") (pinfunction "P_B29") (pintype "passive"))
      (node (ref "X2") (pin "B3") (pinfunction "P_B3") (pintype "passive"))
      (node (ref "X3") (pin "B29") (pinfunction "P_B29") (pintype "passive"))
      (node (ref "X3") (pin "B3") (pinfunction "P_B3") (pintype "passive"))
      (node (ref "X4") (pin "5") (pinfunction "5_5") (pintype "passive"))
    )
    (net (code "3") (name "2MHZ") (class "Default")
      (node (ref "IC3") (pin "9") (pinfunction "Q_9") (pintype "output"))
      (node (ref "JP5") (pin "1") (pinfunction "1_1") (pintype "passive"))
    )
    (net (code "4") (name "2PA0") (class "Default")
      (node (ref "IC14") (pin "20") (pinfunction "(PCINT0/ADC0)PA0_20") (pintype "bidirectional"))
      (node (ref "IC18") (pin "2") (pinfunction "PA0_2") (pintype "bidirectional"))
      (node (ref "JP10") (pin "3") (pinfunction "3_3") (pintype "passive"))
    )
    (net (code "5") (name "2PA1") (class "Default")
      (node (ref "IC14") (pin "19") (pinfunction "(PCINT1/ADC1)PA1_19") (pintype "bidirectional"))
      (node (ref "IC18") (pin "3") (pinfunction "PA1_3") (pintype "bidirectional"))
      (node (ref "JP10") (pin "5") (pinfunction "5_5") (pintype "passive"))
    )
    (net (code "6") (name "2PA2") (class "Default")
      (node (ref "IC14") (pin "18") (pinfunction "(PCINT2/ADC2)PA2_18") (pintype "bidirectional"))
      (node (ref "IC18") (pin "4") (pinfunction "PA2_4") (pintype "bidirectional"))
      (node (ref "JP10") (pin "7") (pinfunction "7_7") (pintype "passive"))
    )
    (net (code "7") (name "2PA3") (class "Default")
      (node (ref "IC14") (pin "17") (pinfunction "(PCINT3/AREF)PA3_17") (pintype "bidirectional"))
      (node (ref "IC18") (pin "5") (pinfunction "PA3_5") (pintype "bidirectional"))
      (node (ref "JP10") (pin "9") (pinfunction "9_9") (pintype "passive"))
    )
    (net (code "8") (name "2PA4") (class "Default")
      (node (ref "IC14") (pin "14") (pinfunction "(PCINT4/ADC3)PA4_14") (pintype "bidirectional"))
      (node (ref "IC18") (pin "6") (pinfunction "PA4_6") (pintype "bidirectional"))
      (node (ref "JP10") (pin "11") (pinfunction "11_11") (pintype "passive"))
    )
    (net (code "9") (name "2PA5") (class "Default")
      (node (ref "IC14") (pin "13") (pinfunction "(PCINT5/ADC4)PA5_13") (pintype "bidirectional"))
      (node (ref "IC18") (pin "7") (pinfunction "PA5_7") (pintype "bidirectional"))
      (node (ref "JP10") (pin "13") (pinfunction "13_13") (pintype "passive"))
    )
    (net (code "10") (name "2PA6") (class "Default")
      (node (ref "IC14") (pin "12") (pinfunction "(PCINT6/AIN0/ADC5)PA6_12") (pintype "bidirectional"))
      (node (ref "IC18") (pin "8") (pinfunction "PA6_8") (pintype "bidirectional"))
      (node (ref "JP10") (pin "15") (pinfunction "15_15") (pintype "passive"))
    )
    (net (code "11") (name "2PA7") (class "Default")
      (node (ref "IC14") (pin "11") (pinfunction "(PCINT7/AIN1/ADC6)PA7_11") (pintype "bidirectional"))
      (node (ref "IC18") (pin "9") (pinfunction "PA7_9") (pintype "bidirectional"))
      (node (ref "JP10") (pin "17") (pinfunction "17_17") (pintype "passive"))
    )
    (net (code "12") (name "2PB0") (class "Default")
      (node (ref "IC14") (pin "8") (pinfunction "PB5(ADC8/XTAL2/PCINT13)_8") (pintype "bidirectional"))
      (node (ref "IC18") (pin "10") (pinfunction "PB0_10") (pintype "bidirectional"))
      (node (ref "JP10") (pin "4") (pinfunction "4_4") (pintype "passive"))
    )
    (net (code "13") (name "2PB1") (class "Default")
      (node (ref "IC14") (pin "9") (pinfunction "PB6(ADC9/INT0/T0/PCINT14)_9") (pintype "bidirectional"))
      (node (ref "IC18") (pin "11") (pinfunction "PB1_11") (pintype "bidirectional"))
      (node (ref "JP10") (pin "6") (pinfunction "6_6") (pintype "passive"))
    )
    (net (code "14") (name "2PB2") (class "Default")
      (node (ref "C24") (pin "2") (pinfunction "2_2") (pintype "passive"))
      (node (ref "IC18") (pin "12") (pinfunction "PB2_12") (pintype "bidirectional"))
      (node (ref "J3") (pin "1") (pinfunction "1_1") (pintype "passive"))
      (node (ref "JP10") (pin "8") (pinfunction "8_8") (pintype "passive"))
      (node (ref "RN2") (pin "9") (pinfunction "9_9") (pintype "passive"))
    )
    (net (code "15") (name "2PB3") (class "Default")
      (node (ref "C26") (pin "2") (pinfunction "2_2") (pintype "passive"))
      (node (ref "IC18") (pin "13") (pinfunction "PB3_13") (pintype "bidirectional"))
      (node (ref "J3") (pin "2") (pinfunction "2_2") (pintype "passive"))
      (node (ref "JP10") (pin "10") (pinfunction "10_10") (pintype "passive"))
      (node (ref "RN2") (pin "8") (pinfunction "8_8") (pintype "passive"))
    )
    (net (code "16") (name "2PB4") (class "Default")
      (node (ref "C25") (pin "1") (pinfunction "1_1") (pintype "passive"))
      (node (ref "IC18") (pin "14") (pinfunction "PB4_14") (pintype "bidirectional"))
      (node (ref "J3") (pin "3") (pinfunction "3_3") (pintype "passive"))
      (node (ref "JP10") (pin "12") (pinfunction "12_12") (pintype "passive"))
      (node (ref "RN2") (pin "7") (pinfunction "7_7") (pintype "passive"))
    )
    (net (code "17") (name "2PB5") (class "Default")
      (node (ref "C27") (pin "1") (pinfunction "1_1") (pintype "passive"))
      (node (ref "IC18") (pin "15") (pinfunction "PB5_15") (pintype "bidirectional"))
      (node (ref "J3") (pin "4") (pinfunction "4_4") (pintype "passive"))
      (node (ref "JP10") (pin "14") (pinfunction "14_14") (pintype "passive"))
      (node (ref "RN2") (pin "6") (pinfunction "6_6") (pintype "passive"))
    )
    (net (code "18") (name "2PB6") (class "Default")
      (node (ref "C28") (pin "2") (pinfunction "2_2") (pintype "passive"))
      (node (ref "IC18") (pin "16") (pinfunction "PB6_16") (pintype "bidirectional"))
      (node (ref "J3") (pin "6") (pinfunction "6_6") (pintype "passive"))
      (node (ref "JP10") (pin "16") (pinfunction "16_16") (pintype "passive"))
      (node (ref "RN2") (pin "5") (pinfunction "5_5") (pintype "passive"))
    )
    (net (code "19") (name "2PB7") (class "Default")
      (node (ref "IC18") (pin "17") (pinfunction "PB7_17") (pintype "bidirectional"))
      (node (ref "JP10") (pin "18") (pinfunction "18_18") (pintype "passive"))
      (node (ref "RN2") (pin "4") (pinfunction "4_4") (pintype "passive"))
    )
    (net (code "20") (name "4MHZ") (class "Default")
      (node (ref "IC3") (pin "11") (pinfunction "CLK_11") (pintype "input"))
      (node (ref "IC3") (pin "5") (pinfunction "Q_5") (pintype "output"))
      (node (ref "JP4") (pin "1") (pinfunction "1_1") (pintype "passive"))
    )
    (net (code "21") (name "8MHZ") (class "Default")
      (node (ref "IC2") (pin "9") (pinfunction "Q_9") (pintype "output"))
      (node (ref "IC3") (pin "3") (pinfunction "CLK_3") (pintype "input"))
      (node (ref "JP3") (pin "1") (pinfunction "1_1") (pintype "passive"))
    )
    (net (code "22") (name "16MHZ") (class "Default")
      (node (ref "IC2") (pin "11") (pinfunction "CLK_11") (pintype "input"))
      (node (ref "IC2") (pin "5") (pinfunction "Q_5") (pintype "output"))
      (node (ref "JP2") (pin "1") (pinfunction "1_1") (pintype "passive"))
    )
    (net (code "23") (name "32MHZ") (class "Default")
      (node (ref "IC2") (pin "3") (pinfunction "CLK_3") (pintype "input"))
      (node (ref "QG1") (pin "8") (pinfunction "OUT_8") (pintype "output"))
      (node (ref "X1") (pin "B18") (pinfunction "P_B18") (pintype "passive"))
      (node (ref "X2") (pin "B18") (pinfunction "P_B18") (pintype "passive"))
      (node (ref "X3") (pin "B18") (pinfunction "P_B18") (pintype "passive"))
    )
    (net (code "24") (name "A0") (class "Default")
      (node (ref "IC16") (pin "38") (pinfunction "RS0_38") (pintype "input"))
      (node (ref "IC18") (pin "38") (pinfunction "RS0_38") (pintype "input"))
      (node (ref "IC19") (pin "13") (pinfunction "RS0_13") (pintype "input"))
      (node (ref "IC4") (pin "9") (pinfunction "A0_9") (pintype "bidirectional"))
      (node (ref "IC5") (pin "10") (pinfunction "A0_10") (pintype "input"))
      (node (ref "IC6") (pin "10") (pinfunction "A0_10") (pintype "input"))
      (node (ref "IC7") (pin "10") (pinfunction "A0_10") (pintype "input"))
      (node (ref "JP6") (pin "19") (pinfunction "19_19") (pintype "passive"))
      (node (ref "X1") (pin "A31") (pinfunction "P_A31") (pintype "passive"))
      (node (ref "X2") (pin "A31") (pinfunction "P_A31") (pintype "passive"))
      (node (ref "X3") (pin "A31") (pinfunction "P_A31") (pintype "passive"))
    )
    (net (code "25") (name "A1") (class "Default")
      (node (ref "IC16") (pin "37") (pinfunction "RS1_37") (pintype "input"))
      (node (ref "IC18") (pin "37") (pinfunction "RS1_37") (pintype "input"))
      (node (ref "IC19") (pin "14") (pinfunction "RS1_14") (pintype "input"))
      (node (ref "IC4") (pin "10") (pinfunction "A1_10") (pintype "bidirectional"))
      (node (ref "IC5") (pin "9") (pinfunction "A1_9") (pintype "input"))
      (node (ref "IC6") (pin "9") (pinfunction "A1_9") (pintype "input"))
      (node (ref "IC7") (pin "9") (pinfunction "A1_9") (pintype "input"))
      (node (ref "JP6") (pin "20") (pinfunction "20_20") (pintype "passive"))
      (node (ref "X1") (pin "A30") (pinfunction "P_A30") (pintype "passive"))
      (node (ref "X2") (pin "A30") (pinfunction "P_A30") (pintype "passive"))
      (node (ref "X3") (pin "A30") (pinfunction "P_A30") (pintype "passive"))
    )
    (net (code "26") (name "A2") (class "Default")
      (node (ref "IC16") (pin "36") (pinfunction "RS2_36") (pintype "input"))
      (node (ref "IC18") (pin "36") (pinfunction "RS2_36") (pintype "input"))
      (node (ref "IC4") (pin "11") (pinfunction "A2_11") (pintype "bidirectional"))
      (node (ref "IC5") (pin "8") (pinfunction "A2_8") (pintype "input"))
      (node (ref "IC6") (pin "8") (pinfunction "A2_8") (pintype "input"))
      (node (ref "IC7") (pin "8") (pinfunction "A2_8") (pintype "input"))
      (node (ref "JP6") (pin "17") (pinfunction "17_17") (pintype "passive"))
      (node (ref "X1") (pin "A29") (pinfunction "P_A29") (pintype "passive"))
      (node (ref "X2") (pin "A29") (pinfunction "P_A29") (pintype "passive"))
      (node (ref "X3") (pin "A29") (pinfunction "P_A29") (pintype "passive"))
    )
    (net (code "27") (name "A3") (class "Default")
      (node (ref "IC16") (pin "35") (pinfunction "RS3_35") (pintype "input"))
      (node (ref "IC18") (pin "35") (pinfunction "RS3_35") (pintype "input"))
      (node (ref "IC4") (pin "12") (pinfunction "A3_12") (pintype "bidirectional"))
      (node (ref "IC5") (pin "7") (pinfunction "A3_7") (pintype "input"))
      (node (ref "IC6") (pin "7") (pinfunction "A3_7") (pintype "input"))
      (node (ref "IC7") (pin "7") (pinfunction "A3_7") (pintype "input"))
      (node (ref "JP6") (pin "18") (pinfunction "18_18") (pintype "passive"))
      (node (ref "X1") (pin "A28") (pinfunction "P_A28") (pintype "passive"))
      (node (ref "X2") (pin "A28") (pinfunction "P_A28") (pintype "passive"))
      (node (ref "X3") (pin "A28") (pinfunction "P_A28") (pintype "passive"))
    )
    (net (code "28") (name "A4") (class "Default")
      (node (ref "IC4") (pin "13") (pinfunction "A4_13") (pintype "bidirectional"))
      (node (ref "IC5") (pin "6") (pinfunction "A4_6") (pintype "input"))
      (node (ref "IC6") (pin "6") (pinfunction "A4_6") (pintype "input"))
      (node (ref "IC7") (pin "6") (pinfunction "A4_6") (pintype "input"))
      (node (ref "JP6") (pin "15") (pinfunction "15_15") (pintype "passive"))
      (node (ref "X1") (pin "A27") (pinfunction "P_A27") (pintype "passive"))
      (node (ref "X2") (pin "A27") (pinfunction "P_A27") (pintype "passive"))
      (node (ref "X3") (pin "A27") (pinfunction "P_A27") (pintype "passive"))
    )
    (net (code "29") (name "A5") (class "Default")
      (node (ref "IC4") (pin "14") (pinfunction "A5_14") (pintype "bidirectional"))
      (node (ref "IC5") (pin "5") (pinfunction "A5_5") (pintype "input"))
      (node (ref "IC6") (pin "5") (pinfunction "A5_5") (pintype "input"))
      (node (ref "IC7") (pin "5") (pinfunction "A5_5") (pintype "input"))
      (node (ref "X1") (pin "A26") (pinfunction "P_A26") (pintype "passive"))
      (node (ref "X2") (pin "A26") (pinfunction "P_A26") (pintype "passive"))
      (node (ref "X3") (pin "A26") (pinfunction "P_A26") (pintype "passive"))
    )
    (net (code "30") (name "A6") (class "Default")
      (node (ref "IC4") (pin "15") (pinfunction "A6_15") (pintype "bidirectional"))
      (node (ref "IC5") (pin "4") (pinfunction "A6_4") (pintype "input"))
      (node (ref "IC6") (pin "4") (pinfunction "A6_4") (pintype "input"))
      (node (ref "IC7") (pin "4") (pinfunction "A6_4") (pintype "input"))
      (node (ref "X1") (pin "A25") (pinfunction "P_A25") (pintype "passive"))
      (node (ref "X2") (pin "A25") (pinfunction "P_A25") (pintype "passive"))
      (node (ref "X3") (pin "A25") (pinfunction "P_A25") (pintype "passive"))
    )
    (net (code "31") (name "A7") (class "Default")
      (node (ref "IC10") (pin "4") (pinfunction "I0_4") (pintype "input"))
      (node (ref "IC10") (pin "5") (pinfunction "I1_5") (pintype "input"))
      (node (ref "IC16") (pin "24") (pinfunction "CS1_24") (pintype "input"))
      (node (ref "IC21") (pin "5") (pinfunction "I1_5") (pintype "input"))
      (node (ref "IC4") (pin "16") (pinfunction "A7_16") (pintype "bidirectional"))
      (node (ref "IC5") (pin "3") (pinfunction "A7_3") (pintype "input"))
      (node (ref "IC6") (pin "3") (pinfunction "A7_3") (pintype "input"))
      (node (ref "IC7") (pin "3") (pinfunction "A7_3") (pintype "input"))
      (node (ref "X1") (pin "A24") (pinfunction "P_A24") (pintype "passive"))
      (node (ref "X2") (pin "A24") (pinfunction "P_A24") (pintype "passive"))
      (node (ref "X3") (pin "A24") (pinfunction "P_A24") (pintype "passive"))
    )
    (net (code "32") (name "A8") (class "Default")
      (node (ref "IC4") (pin "17") (pinfunction "A8_17") (pintype "bidirectional"))
      (node (ref "IC5") (pin "25") (pinfunction "A8_25") (pintype "input"))
      (node (ref "IC6") (pin "25") (pinfunction "A8_25") (pintype "input"))
      (node (ref "IC7") (pin "25") (pinfunction "A8_25") (pintype "input"))
      (node (ref "IC9") (pin "14") (pinfunction "A_14") (pintype "input"))
      (node (ref "X1") (pin "A23") (pinfunction "P_A23") (pintype "passive"))
      (node (ref "X2") (pin "A23") (pinfunction "P_A23") (pintype "passive"))
      (node (ref "X3") (pin "A23") (pinfunction "P_A23") (pintype "passive"))
    )
    (net (code "33") (name "A9") (class "Default")
      (node (ref "IC4") (pin "18") (pinfunction "A9_18") (pintype "bidirectional"))
      (node (ref "IC5") (pin "24") (pinfunction "A9_24") (pintype "input"))
      (node (ref "IC6") (pin "24") (pinfunction "A9_24") (pintype "input"))
      (node (ref "IC7") (pin "24") (pinfunction "A9_24") (pintype "input"))
      (node (ref "IC9") (pin "13") (pinfunction "B_13") (pintype "input"))
      (node (ref "X1") (pin "A22") (pinfunction "P_A22") (pintype "passive"))
      (node (ref "X2") (pin "A22") (pinfunction "P_A22") (pintype "passive"))
      (node (ref "X3") (pin "A22") (pinfunction "P_A22") (pintype "passive"))
    )
    (net (code "34") (name "A10") (class "Default")
      (node (ref "IC4") (pin "19") (pinfunction "A10_19") (pintype "bidirectional"))
      (node (ref "IC5") (pin "21") (pinfunction "A10_21") (pintype "input"))
      (node (ref "IC6") (pin "21") (pinfunction "A10_21") (pintype "input"))
      (node (ref "IC7") (pin "21") (pinfunction "A10_21") (pintype "input"))
      (node (ref "IC9") (pin "2") (pinfunction "A_2") (pintype "input"))
      (node (ref "X1") (pin "A21") (pinfunction "P_A21") (pintype "passive"))
      (node (ref "X2") (pin "A21") (pinfunction "P_A21") (pintype "passive"))
      (node (ref "X3") (pin "A21") (pinfunction "P_A21") (pintype "passive"))
    )
    (net (code "35") (name "A11") (class "Default")
      (node (ref "IC4") (pin "20") (pinfunction "A11_20") (pintype "bidirectional"))
      (node (ref "IC5") (pin "23") (pinfunction "A11_23") (pintype "input"))
      (node (ref "IC6") (pin "23") (pinfunction "A11_23") (pintype "input"))
      (node (ref "IC7") (pin "23") (pinfunction "A11_23") (pintype "input"))
      (node (ref "IC9") (pin "3") (pinfunction "B_3") (pintype "input"))
      (node (ref "X1") (pin "A20") (pinfunction "P_A20") (pintype "passive"))
      (node (ref "X2") (pin "A20") (pinfunction "P_A20") (pintype "passive"))
      (node (ref "X3") (pin "A20") (pinfunction "P_A20") (pintype "passive"))
    )
    (net (code "36") (name "A12") (class "Default")
      (node (ref "IC11") (pin "14") (pinfunction "A_14") (pintype "input"))
      (node (ref "IC4") (pin "22") (pinfunction "A12_22") (pintype "bidirectional"))
      (node (ref "IC5") (pin "2") (pinfunction "A12_2") (pintype "input"))
      (node (ref "IC6") (pin "2") (pinfunction "A12_2") (pintype "input"))
      (node (ref "IC7") (pin "2") (pinfunction "A12_2") (pintype "input"))
      (node (ref "X1") (pin "A19") (pinfunction "P_A19") (pintype "passive"))
      (node (ref "X2") (pin "A19") (pinfunction "P_A19") (pintype "passive"))
      (node (ref "X3") (pin "A19") (pinfunction "P_A19") (pintype "passive"))
    )
    (net (code "37") (name "A13") (class "Default")
      (node (ref "IC11") (pin "13") (pinfunction "B_13") (pintype "input"))
      (node (ref "IC12") (pin "4") (pinfunction "I0_4") (pintype "input"))
      (node (ref "IC4") (pin "23") (pinfunction "A13_23") (pintype "bidirectional"))
      (node (ref "IC6") (pin "26") (pinfunction "A13_26") (pintype "input"))
      (node (ref "IC7") (pin "26") (pinfunction "A13_26") (pintype "input"))
      (node (ref "X1") (pin "A18") (pinfunction "P_A18") (pintype "passive"))
      (node (ref "X2") (pin "A18") (pinfunction "P_A18") (pintype "passive"))
      (node (ref "X3") (pin "A18") (pinfunction "P_A18") (pintype "passive"))
    )
    (net (code "38") (name "A14") (class "Default")
      (node (ref "IC11") (pin "2") (pinfunction "A_2") (pintype "input"))
      (node (ref "IC4") (pin "24") (pinfunction "A14_24") (pintype "bidirectional"))
      (node (ref "IC6") (pin "1") (pinfunction "A14_1") (pintype "input"))
      (node (ref "X1") (pin "A17") (pinfunction "P_A17") (pintype "passive"))
      (node (ref "X2") (pin "A17") (pinfunction "P_A17") (pintype "passive"))
      (node (ref "X3") (pin "A17") (pinfunction "P_A17") (pintype "passive"))
    )
    (net (code "39") (name "A15") (class "Default")
      (node (ref "IC11") (pin "3") (pinfunction "B_3") (pintype "input"))
      (node (ref "IC4") (pin "25") (pinfunction "A15_25") (pintype "bidirectional"))
      (node (ref "IC6") (pin "20") (pinfunction "~{CS}_20") (pintype "input"))
      (node (ref "X1") (pin "A16") (pinfunction "P_A16") (pintype "passive"))
      (node (ref "X2") (pin "A16") (pinfunction "P_A16") (pintype "passive"))
      (node (ref "X3") (pin "A16") (pinfunction "P_A16") (pintype "passive"))
    )
    (net (code "40") (name "ACIA_CSH") (class "Default")
      (node (ref "IC19") (pin "2") (pinfunction "CS0_2") (pintype "input"))
      (node (ref "R17") (pin "1") (pinfunction "1_1") (pintype "passive"))
    )
    (net (code "41") (name "AVR_RST") (class "Default")
      (node (ref "IC14") (pin "10") (pinfunction "PB7(ADC10/~{RESET}/PCINT15)_10") (pintype "bidirectional"))
      (node (ref "J2") (pin "5") (pinfunction "5_5") (pintype "passive"))
      (node (ref "SJ3") (pin "2") (pinfunction "2_2") (pintype "passive"))
    )
    (net (code "42") (name "BE") (class "Default")
      (node (ref "IC4") (pin "36") (pinfunction "BE_36") (pintype "input"))
      (node (ref "R9") (pin "2") (pinfunction "2_2") (pintype "passive"))
      (node (ref "X1") (pin "A11") (pinfunction "P_A11") (pintype "passive"))
      (node (ref "X2") (pin "A11") (pinfunction "P_A11") (pintype "passive"))
      (node (ref "X3") (pin "A11") (pinfunction "P_A11") (pintype "passive"))
    )
    (net (code "43") (name "C-F") (class "Default")
      (node (ref "IC12") (pin "3") (pinfunction "O_3") (pintype "output"))
      (node (ref "IC12") (pin "5") (pinfunction "I1_5") (pintype "input"))
    )
    (net (code "44") (name "CA1") (class "Default")
      (node (ref "IC16") (pin "40") (pinfunction "CA1_40") (pintype "bidirectional"))
      (node (ref "JP9") (pin "1") (pinfunction "1_1") (pintype "passive"))
    )
    (net (code "45") (name "CA2") (class "Default")
      (node (ref "IC16") (pin "39") (pinfunction "CA2_39") (pintype "bidirectional"))
      (node (ref "JP9") (pin "3") (pinfunction "3_3") (pintype "passive"))
    )
    (net (code "46") (name "CB1") (class "Default")
      (node (ref "IC16") (pin "18") (pinfunction "CB1_18") (pintype "bidirectional"))
      (node (ref "JP9") (pin "2") (pinfunction "2_2") (pintype "passive"))
    )
    (net (code "47") (name "CB2") (class "Default")
      (node (ref "IC16") (pin "19") (pinfunction "CB2_19") (pintype "bidirectional"))
      (node (ref "JP9") (pin "4") (pinfunction "4_4") (pintype "passive"))
    )
    (net (code "48") (name "CLK") (class "Default")
      (node (ref "IC4") (pin "37") (pinfunction "PH0-IN_37") (pintype "input"))
      (node (ref "JP13") (pin "1") (pinfunction "1_1") (pintype "passive"))
      (node (ref "X1") (pin "B30") (pinfunction "P_B30") (pintype "passive"))
      (node (ref "X2") (pin "B30") (pinfunction "P_B30") (pintype "passive"))
      (node (ref "X3") (pin "B30") (pinfunction "P_B30") (pintype "passive"))
    )
    (net (code "49") (name "CTS") (class "Default")
      (node (ref "IC19") (pin "9") (pinfunction "CTS_9") (pintype "input"))
      (node (ref "JP11") (pin "7") (pinfunction "7_7") (pintype "passive"))
      (node (ref "JP12") (pin "2") (pinfunction "2_2") (pintype "passive"))
      (node (ref "SJ2") (pin "2") (pinfunction "2_2") (pintype "passive"))
    )
    (net (code "50") (name "D+") (class "Default")
      (node (ref "J4") (pin "A6") (pinfunction "D+_A6") (pintype "bidirectional"))
      (node (ref "J4") (pin "B6") (pinfunction "D+_B6") (pintype "bidirectional"))
      (node (ref "U$1") (pin "13") (pinfunction "USB+_13") (pintype "bidirectional"))
    )
    (net (code "51") (name "D-") (class "Default")
      (node (ref "J4") (pin "A7") (pinfunction "D-_A7") (pintype "bidirectional"))
      (node (ref "J4") (pin "B7") (pinfunction "D-_B7") (pintype "bidirectional"))
      (node (ref "U$1") (pin "12") (pinfunction "USB-_12") (pintype "bidirectional"))
    )
    (net (code "52") (name "D0") (class "Default")
      (node (ref "IC16") (pin "33") (pinfunction "D0_33") (pintype "bidirectional"))
      (node (ref "IC18") (pin "33") (pinfunction "D0_33") (pintype "bidirectional"))
      (node (ref "IC19") (pin "18") (pinfunction "D0_18") (pintype "bidirectional"))
      (node (ref "IC27") (pin "19") (pinfunction "1Q_19") (pintype "tri_state"))
      (node (ref "IC4") (pin "33") (pinfunction "D0_33") (pintype "bidirectional"))
      (node (ref "IC5") (pin "11") (pinfunction "D0_11") (pintype "tri_state"))
      (node (ref "IC6") (pin "11") (pinfunction "I/O0_11") (pintype "bidirectional"))
      (node (ref "IC7") (pin "11") (pinfunction "I/O0_11") (pintype "bidirectional"))
      (node (ref "JP6") (pin "10") (pinfunction "10_10") (pintype "passive"))
      (node (ref "X1") (pin "A9") (pinfunction "P_A9") (pintype "passive"))
      (node (ref "X2") (pin "A9") (pinfunction "P_A9") (pintype "passive"))
      (node (ref "X3") (pin "A9") (pinfunction "P_A9") (pintype "passive"))
    )
    (net (code "53") (name "D1") (class "Default")
      (node (ref "IC16") (pin "32") (pinfunction "D1_32") (pintype "bidirectional"))
      (node (ref "IC18") (pin "32") (pinfunction "D1_32") (pintype "bidirectional"))
      (node (ref "IC19") (pin "19") (pinfunction "D1_19") (pintype "bidirectional"))
      (node (ref "IC27") (pin "18") (pinfunction "2Q_18") (pintype "tri_state"))
      (node (ref "IC4") (pin "32") (pinfunction "D1_32") (pintype "bidirectional"))
      (node (ref "IC5") (pin "12") (pinfunction "D1_12") (pintype "tri_state"))
      (node (ref "IC6") (pin "12") (pinfunction "I/O1_12") (pintype "bidirectional"))
      (node (ref "IC7") (pin "12") (pinfunction "I/O1_12") (pintype "bidirectional"))
      (node (ref "JP6") (pin "9") (pinfunction "9_9") (pintype "passive"))
      (node (ref "X1") (pin "A8") (pinfunction "P_A8") (pintype "passive"))
      (node (ref "X2") (pin "A8") (pinfunction "P_A8") (pintype "passive"))
      (node (ref "X3") (pin "A8") (pinfunction "P_A8") (pintype "passive"))
    )
    (net (code "54") (name "D2") (class "Default")
      (node (ref "IC16") (pin "31") (pinfunction "D2_31") (pintype "bidirectional"))
      (node (ref "IC18") (pin "31") (pinfunction "D2_31") (pintype "bidirectional"))
      (node (ref "IC19") (pin "20") (pinfunction "D2_20") (pintype "bidirectional"))
      (node (ref "IC27") (pin "17") (pinfunction "3Q_17") (pintype "tri_state"))
      (node (ref "IC4") (pin "31") (pinfunction "D2_31") (pintype "bidirectional"))
      (node (ref "IC5") (pin "13") (pinfunction "D2_13") (pintype "tri_state"))
      (node (ref "IC6") (pin "13") (pinfunction "I/O2_13") (pintype "bidirectional"))
      (node (ref "IC7") (pin "13") (pinfunction "I/O2_13") (pintype "bidirectional"))
      (node (ref "JP6") (pin "8") (pinfunction "8_8") (pintype "passive"))
      (node (ref "X1") (pin "A7") (pinfunction "P_A7") (pintype "passive"))
      (node (ref "X2") (pin "A7") (pinfunction "P_A7") (pintype "passive"))
      (node (ref "X3") (pin "A7") (pinfunction "P_A7") (pintype "passive"))
    )
    (net (code "55") (name "D3") (class "Default")
      (node (ref "IC16") (pin "30") (pinfunction "D3_30") (pintype "bidirectional"))
      (node (ref "IC18") (pin "30") (pinfunction "D3_30") (pintype "bidirectional"))
      (node (ref "IC19") (pin "21") (pinfunction "D3_21") (pintype "bidirectional"))
      (node (ref "IC27") (pin "16") (pinfunction "4Q_16") (pintype "tri_state"))
      (node (ref "IC4") (pin "30") (pinfunction "D3_30") (pintype "bidirectional"))
      (node (ref "IC5") (pin "15") (pinfunction "D3_15") (pintype "tri_state"))
      (node (ref "IC6") (pin "15") (pinfunction "I/O3_15") (pintype "bidirectional"))
      (node (ref "IC7") (pin "15") (pinfunction "I/O3_15") (pintype "bidirectional"))
      (node (ref "JP6") (pin "7") (pinfunction "7_7") (pintype "passive"))
      (node (ref "X1") (pin "A6") (pinfunction "P_A6") (pintype "passive"))
      (node (ref "X2") (pin "A6") (pinfunction "P_A6") (pintype "passive"))
      (node (ref "X3") (pin "A6") (pinfunction "P_A6") (pintype "passive"))
    )
    (net (code "56") (name "D4") (class "Default")
      (node (ref "IC16") (pin "29") (pinfunction "D4_29") (pintype "bidirectional"))
      (node (ref "IC18") (pin "29") (pinfunction "D4_29") (pintype "bidirectional"))
      (node (ref "IC19") (pin "22") (pinfunction "D4_22") (pintype "bidirectional"))
      (node (ref "IC27") (pin "15") (pinfunction "5Q_15") (pintype "tri_state"))
      (node (ref "IC4") (pin "29") (pinfunction "D4_29") (pintype "bidirectional"))
      (node (ref "IC5") (pin "16") (pinfunction "D4_16") (pintype "tri_state"))
      (node (ref "IC6") (pin "16") (pinfunction "I/O4_16") (pintype "bidirectional"))
      (node (ref "IC7") (pin "16") (pinfunction "I/O4_16") (pintype "bidirectional"))
      (node (ref "JP6") (pin "6") (pinfunction "6_6") (pintype "passive"))
      (node (ref "X1") (pin "A5") (pinfunction "P_A5") (pintype "passive"))
      (node (ref "X2") (pin "A5") (pinfunction "P_A5") (pintype "passive"))
      (node (ref "X3") (pin "A5") (pinfunction "P_A5") (pintype "passive"))
    )
    (net (code "57") (name "D5") (class "Default")
      (node (ref "IC16") (pin "28") (pinfunction "D5_28") (pintype "bidirectional"))
      (node (ref "IC18") (pin "28") (pinfunction "D5_28") (pintype "bidirectional"))
      (node (ref "IC19") (pin "23") (pinfunction "D5_23") (pintype "bidirectional"))
      (node (ref "IC27") (pin "14") (pinfunction "6Q_14") (pintype "tri_state"))
      (node (ref "IC4") (pin "28") (pinfunction "D5_28") (pintype "bidirectional"))
      (node (ref "IC5") (pin "17") (pinfunction "D5_17") (pintype "tri_state"))
      (node (ref "IC6") (pin "17") (pinfunction "I/O5_17") (pintype "bidirectional"))
      (node (ref "IC7") (pin "17") (pinfunction "I/O5_17") (pintype "bidirectional"))
      (node (ref "JP6") (pin "5") (pinfunction "5_5") (pintype "passive"))
      (node (ref "X1") (pin "A4") (pinfunction "P_A4") (pintype "passive"))
      (node (ref "X2") (pin "A4") (pinfunction "P_A4") (pintype "passive"))
      (node (ref "X3") (pin "A4") (pinfunction "P_A4") (pintype "passive"))
    )
    (net (code "58") (name "D6") (class "Default")
      (node (ref "IC16") (pin "27") (pinfunction "D6_27") (pintype "bidirectional"))
      (node (ref "IC18") (pin "27") (pinfunction "D6_27") (pintype "bidirectional"))
      (node (ref "IC19") (pin "24") (pinfunction "D6_24") (pintype "bidirectional"))
      (node (ref "IC27") (pin "13") (pinfunction "7Q_13") (pintype "tri_state"))
      (node (ref "IC4") (pin "27") (pinfunction "D6_27") (pintype "bidirectional"))
      (node (ref "IC5") (pin "18") (pinfunction "D6_18") (pintype "tri_state"))
      (node (ref "IC6") (pin "18") (pinfunction "I/O6_18") (pintype "bidirectional"))
      (node (ref "IC7") (pin "18") (pinfunction "I/O6_18") (pintype "bidirectional"))
      (node (ref "JP6") (pin "4") (pinfunction "4_4") (pintype "passive"))
      (node (ref "X1") (pin "A3") (pinfunction "P_A3") (pintype "passive"))
      (node (ref "X2") (pin "A3") (pinfunction "P_A3") (pintype "passive"))
      (node (ref "X3") (pin "A3") (pinfunction "P_A3") (pintype "passive"))
    )
    (net (code "59") (name "D7") (class "Default")
      (node (ref "IC16") (pin "26") (pinfunction "D7_26") (pintype "bidirectional"))
      (node (ref "IC18") (pin "26") (pinfunction "D7_26") (pintype "bidirectional"))
      (node (ref "IC19") (pin "25") (pinfunction "D7_25") (pintype "bidirectional"))
      (node (ref "IC27") (pin "12") (pinfunction "8Q_12") (pintype "tri_state"))
      (node (ref "IC4") (pin "26") (pinfunction "D7_26") (pintype "bidirectional"))
      (node (ref "IC5") (pin "19") (pinfunction "D7_19") (pintype "tri_state"))
      (node (ref "IC6") (pin "19") (pinfunction "I/O7_19") (pintype "bidirectional"))
      (node (ref "IC7") (pin "19") (pinfunction "I/O7_19") (pintype "bidirectional"))
      (node (ref "JP6") (pin "3") (pinfunction "3_3") (pintype "passive"))
      (node (ref "X1") (pin "A2") (pinfunction "P_A2") (pintype "passive"))
      (node (ref "X2") (pin "A2") (pinfunction "P_A2") (pintype "passive"))
      (node (ref "X3") (pin "A2") (pinfunction "P_A2") (pintype "passive"))
    )
    (net (code "60") (name "DTR") (class "Default")
      (node (ref "JP11") (pin "1") (pinfunction "1_1") (pintype "passive"))
      (node (ref "SJ1") (pin "2") (pinfunction "2_2") (pintype "passive"))
    )
    (net (code "61") (name "E-F") (class "Default")
      (node (ref "IC12") (pin "12") (pinfunction "I0_12") (pintype "input"))
      (node (ref "IC12") (pin "8") (pinfunction "O_8") (pintype "output"))
    )
    (net (code "62") (name "GND") (class "Default")
      (node (ref "C1") (pin "-") (pinfunction "-_-") (pintype "passive"))
      (node (ref "C10") (pin "2") (pinfunction "2_2") (pintype "passive"))
      (node (ref "C11") (pin "2") (pinfunction "2_2") (pintype "passive"))
      (node (ref "C12") (pin "2") (pinfunction "2_2") (pintype "passive"))
      (node (ref "C13") (pin "2") (pinfunction "2_2") (pintype "passive"))
      (node (ref "C14") (pin "2") (pinfunction "2_2") (pintype "passive"))
      (node (ref "C15") (pin "2") (pinfunction "2_2") (pintype "passive"))
      (node (ref "C16") (pin "2") (pinfunction "2_2") (pintype "passive"))
      (node (ref "C17") (pin "1") (pinfunction "1_1") (pintype "passive"))
      (node (ref "C18") (pin "2") (pinfunction "2_2") (pintype "passive"))
      (node (ref "C2") (pin "2") (pinfunction "2_2") (pintype "passive"))
      (node (ref "C20") (pin "2") (pinfunction "2_2") (pintype "passive"))
      (node (ref "C21") (pin "2") (pinfunction "2_2") (pintype "passive"))
      (node (ref "C22") (pin "2") (pinfunction "2_2") (pintype "passive"))
      (node (ref "C23") (pin "2") (pinfunction "2_2") (pintype "passive"))
      (node (ref "C24") (pin "1") (pinfunction "1_1") (pintype "passive"))
      (node (ref "C25") (pin "2") (pinfunction "2_2") (pintype "passive"))
      (node (ref "C26") (pin "1") (pinfunction "1_1") (pintype "passive"))
      (node (ref "C27") (pin "2") (pinfunction "2_2") (pintype "passive"))
      (node (ref "C28") (pin "1") (pinfunction "1_1") (pintype "passive"))
      (node (ref "C29") (pin "1") (pinfunction "1_1") (pintype "passive"))
      (node (ref "C3") (pin "-") (pinfunction "-_-") (pintype "passive"))
      (node (ref "C30") (pin "1") (pinfunction "1_1") (pintype "passive"))
      (node (ref "C38") (pin "2") (pinfunction "2_2") (pintype "passive"))
      (node (ref "C4") (pin "-") (pinfunction "-_-") (pintype "passive"))
      (node (ref "C5") (pin "2") (pinfunction "2_2") (pintype "passive"))
      (node (ref "C6") (pin "2") (pinfunction "2_2") (pintype "passive"))
      (node (ref "C7") (pin "2") (pinfunction "2_2") (pintype "passive"))
      (node (ref "C8") (pin "2") (pinfunction "2_2") (pintype "passive"))
      (node (ref "C9") (pin "1") (pinfunction "1_1") (pintype "passive"))
      (node (ref "IC1") (pin "1") (pinfunction "GND_1") (pintype "power_in"))
      (node (ref "IC10") (pin "7") (pinfunction "GND_7") (pintype "power_in"))
      (node (ref "IC11") (pin "1") (pinfunction "G_1") (pintype "input"))
      (node (ref "IC11") (pin "8") (pinfunction "GND_8") (pintype "power_in"))
      (node (ref "IC12") (pin "7") (pinfunction "GND_7") (pintype "power_in"))
      (node (ref "IC14") (pin "16") (pinfunction "GND_16") (pintype "power_in"))
      (node (ref "IC14") (pin "6") (pinfunction "GND_6") (pintype "power_in"))
      (node (ref "IC16") (pin "1") (pinfunction "VSS_1") (pintype "power_in"))
      (node (ref "IC17") (pin "5") (pinfunction "EI_5") (pintype "input"))
      (node (ref "IC17") (pin "8") (pinfunction "GND_8") (pintype "power_in"))
      (node (ref "IC18") (pin "1") (pinfunction "VSS_1") (pintype "power_in"))
      (node (ref "IC19") (pin "1") (pinfunction "GND_1") (pintype "power_in"))
      (node (ref "IC19") (pin "16") (pinfunction "DCD_16") (pintype "input"))
      (node (ref "IC19") (pin "17") (pinfunction "DSR_17") (pintype "input"))
      (node (ref "IC2") (pin "7") (pinfunction "GND_7") (pintype "power_in"))
      (node (ref "IC21") (pin "7") (pinfunction "GND_7") (pintype "power_in"))
      (node (ref "IC27") (pin "10") (pinfunction "GND_10") (pintype "power_in"))
      (node (ref "IC27") (pin "2") (pinfunction "1D_2") (pintype "input"))
      (node (ref "IC27") (pin "6") (pinfunction "5D_6") (pintype "input"))
      (node (ref "IC27") (pin "7") (pinfunction "6D_7") (pintype "input"))
      (node (ref "IC27") (pin "8") (pinfunction "7D_8") (pintype "input"))
      (node (ref "IC27") (pin "9") (pinfunction "8D_9") (pintype "input"))
      (node (ref "IC3") (pin "7") (pinfunction "GND_7") (pintype "power_in"))
      (node (ref "IC4") (pin "21") (pinfunction "VSS_21") (pintype "power_in"))
      (node (ref "IC5") (pin "14") (pinfunction "GND_14") (pintype "power_in"))
      (node (ref "IC6") (pin "14") (pinfunction "VSS_14") (pintype "power_in"))
      (node (ref "IC7") (pin "1") (pinfunction "A14_1") (pintype "input"))
      (node (ref "IC7") (pin "14") (pinfunction "VSS_14") (pintype "power_in"))
      (node (ref "IC8") (pin "2") (pinfunction "GND_2") (pintype "bidirectional"))
      (node (ref "IC8") (pin "4") (pinfunction "GND_4") (pintype "bidirectional"))
      (node (ref "IC9") (pin "8") (pinfunction "GND_8") (pintype "power_in"))
      (node (ref "J1") (pin "2") (pinfunction "2_2") (pintype "passive"))
      (node (ref "J1") (pin "3") (pinfunction "3_3") (pintype "passive"))
      (node (ref "J2") (pin "6") (pinfunction "6_6") (pintype "passive"))
      (node (ref "J3") (pin "8") (pinfunction "8_8") (pintype "passive"))
      (node (ref "J4") (pin "GND") (pinfunction "GND_GND") (pintype "bidirectional"))
      (node (ref "J4") (pin "GND2") (pinfunction "GND_GND2") (pintype "bidirectional"))
      (node (ref "J4") (pin "SHLD1") (pinfunction "SHLD_SHLD1") (pintype "bidirectional"))
      (node (ref "J4") (pin "SHLD2") (pinfunction "SHLD_SHLD2") (pintype "bidirectional"))
      (node (ref "J4") (pin "SHLD3") (pinfunction "SHLD_SHLD3") (pintype "bidirectional"))
      (node (ref "J4") (pin "SHLD4") (pinfunction "SHLD_SHLD4") (pintype "bidirectional"))
      (node (ref "J4") (pin "SHLD5") (pinfunction "SHLD_SHLD5") (pintype "bidirectional"))
      (node (ref "J4") (pin "SHLD6") (pinfunction "SHLD_SHLD6") (pintype "bidirectional"))
      (node (ref "J4") (pin "SHLD7") (pinfunction "SHLD_SHLD7") (pintype "bidirectional"))
      (node (ref "J4") (pin "SHLD8") (pinfunction "SHLD_SHLD8") (pintype "bidirectional"))
      (node (ref "JP10") (pin "19") (pinfunction "19_19") (pintype "passive"))
      (node (ref "JP10") (pin "20") (pinfunction "20_20") (pintype "passive"))
      (node (ref "JP11") (pin "6") (pinfunction "6_6") (pintype "passive"))
      (node (ref "JP6") (pin "2") (pinfunction "2_2") (pintype "passive"))
      (node (ref "JP6") (pin "21") (pinfunction "21_21") (pintype "passive"))
      (node (ref "JP6") (pin "22") (pinfunction "22_22") (pintype "passive"))
      (node (ref "JP8") (pin "19") (pinfunction "19_19") (pintype "passive"))
      (node (ref "JP8") (pin "20") (pinfunction "20_20") (pintype "passive"))
      (node (ref "LED1") (pin "K") (pinfunction "C_K") (pintype "passive"))
      (node (ref "LED2") (pin "K") (pinfunction "C_K") (pintype "passive"))
      (node (ref "QG1") (pin "7") (pinfunction "GND_7") (pintype "power_in"))
      (node (ref "S1") (pin "1") (pinfunction "S_1") (pintype "passive"))
      (node (ref "S1") (pin "2") (pinfunction "S1_2") (pintype "passive"))
      (node (ref "S2") (pin "1") (pinfunction "S_1") (pintype "passive"))
      (node (ref "S2") (pin "2") (pinfunction "S1_2") (pintype "passive"))
      (node (ref "S3") (pin "1") (pinfunction "S_1") (pintype "passive"))
      (node (ref "S3") (pin "2") (pinfunction "S1_2") (pintype "passive"))
      (node (ref "SJ2") (pin "1") (pinfunction "1_1") (pintype "passive"))
      (node (ref "U$1") (pin "14") (pinfunction "GND_14") (pintype "bidirectional"))
      (node (ref "X1") (pin "B1") (pinfunction "P_B1") (pintype "passive"))
      (node (ref "X1") (pin "B31") (pinfunction "P_B31") (pintype "passive"))
      (node (ref "X2") (pin "B1") (pinfunction "P_B1") (pintype "passive"))
      (node (ref "X2") (pin "B31") (pinfunction "P_B31") (pintype "passive"))
      (node (ref "X3") (pin "B1") (pinfunction "P_B1") (pintype "passive"))
      (node (ref "X3") (pin "B31") (pinfunction "P_B31") (pintype "passive"))
      (node (ref "X4") (pin "3") (pinfunction "3_3") (pintype "passive"))
      (node (ref "X4") (pin "SH1") (pinfunction "PE1_SH1") (pintype "power_in"))
      (node (ref "X4") (pin "SH2") (pinfunction "PE2_SH2") (pintype "power_in"))
      (node (ref "X4") (pin "SH3") (pinfunction "PE3_SH3") (pintype "power_in"))
    )
    (net (code "63") (name "IRQ") (class "Default")
      (node (ref "IC17") (pin "14") (pinfunction "GS_14") (pintype "output"))
      (node (ref "IC4") (pin "4") (pinfunction "IRQB_4") (pintype "input"))
      (node (ref "LED3") (pin "K") (pinfunction "C_K") (pintype "passive"))
    )
    (net (code "64") (name "IRQ0") (class "Default")
      (node (ref "IC17") (pin "4") (pinfunction "7_4") (pintype "input"))
      (node (ref "IC19") (pin "26") (pinfunction "IRQ_26") (pintype "output"))
      (node (ref "RN1") (pin "2") (pinfunction "2_2") (pintype "passive"))
    )
    (net (code "65") (name "IRQ1") (class "Default")
      (node (ref "IC16") (pin "21") (pinfunction "~{IRQB}_21") (pintype "output"))
      (node (ref "IC17") (pin "3") (pinfunction "6_3") (pintype "input"))
      (node (ref "RN1") (pin "3") (pinfunction "3_3") (pintype "passive"))
    )
    (net (code "66") (name "IRQ2") (class "Default")
      (node (ref "IC17") (pin "2") (pinfunction "5_2") (pintype "input"))
      (node (ref "JP6") (pin "14") (pinfunction "14_14") (pintype "passive"))
      (node (ref "RN1") (pin "4") (pinfunction "4_4") (pintype "passive"))
      (node (ref "X1") (pin "B25") (pinfunction "P_B25") (pintype "passive"))
      (node (ref "X2") (pin "B25") (pinfunction "P_B25") (pintype "passive"))
      (node (ref "X3") (pin "B25") (pinfunction "P_B25") (pintype "passive"))
    )
    (net (code "67") (name "IRQ3") (class "Default")
      (node (ref "IC17") (pin "1") (pinfunction "4_1") (pintype "input"))
      (node (ref "RN1") (pin "5") (pinfunction "5_5") (pintype "passive"))
      (node (ref "X1") (pin "B24") (pinfunction "P_B24") (pintype "passive"))
      (node (ref "X2") (pin "B24") (pinfunction "P_B24") (pintype "passive"))
      (node (ref "X3") (pin "B24") (pinfunction "P_B24") (pintype "passive"))
    )
    (net (code "68") (name "IRQ4") (class "Default")
      (node (ref "IC17") (pin "13") (pinfunction "3_13") (pintype "input"))
      (node (ref "RN1") (pin "6") (pinfunction "6_6") (pintype "passive"))
      (node (ref "X1") (pin "B23") (pinfunction "P_B23") (pintype "passive"))
      (node (ref "X2") (pin "B23") (pinfunction "P_B23") (pintype "passive"))
      (node (ref "X3") (pin "B23") (pinfunction "P_B23") (pintype "passive"))
    )
    (net (code "69") (name "IRQ5") (class "Default")
      (node (ref "IC17") (pin "12") (pinfunction "2_12") (pintype "input"))
      (node (ref "RN1") (pin "7") (pinfunction "7_7") (pintype "passive"))
      (node (ref "X1") (pin "B22") (pinfunction "P_B22") (pintype "passive"))
      (node (ref "X2") (pin "B22") (pinfunction "P_B22") (pintype "passive"))
      (node (ref "X3") (pin "B22") (pinfunction "P_B22") (pintype "passive"))
    )
    (net (code "70") (name "IRQ6") (class "Default")
      (node (ref "IC17") (pin "11") (pinfunction "1_11") (pintype "input"))
      (node (ref "RN1") (pin "8") (pinfunction "8_8") (pintype "passive"))
      (node (ref "X1") (pin "B21") (pinfunction "P_B21") (pintype "passive"))
      (node (ref "X2") (pin "B21") (pinfunction "P_B21") (pintype "passive"))
      (node (ref "X3") (pin "B21") (pinfunction "P_B21") (pintype "passive"))
    )
    (net (code "71") (name "IRQ7") (class "Default")
      (node (ref "IC17") (pin "10") (pinfunction "0_10") (pintype "input"))
      (node (ref "RN1") (pin "9") (pinfunction "9_9") (pintype "passive"))
      (node (ref "S1") (pin "3") (pinfunction "P_3") (pintype "passive"))
      (node (ref "S1") (pin "4") (pinfunction "P1_4") (pintype "passive"))
    )
    (net (code "72") (name "MISO") (class "Default")
      (node (ref "IC14") (pin "2") (pinfunction "(PCINT9/OC1A/DO/MISO)PB1_2") (pintype "bidirectional"))
      (node (ref "J2") (pin "1") (pinfunction "1_1") (pintype "passive"))
    )
    (net (code "73") (name "MLB") (class "Default")
      (node (ref "IC4") (pin "5") (pinfunction "MLB_5") (pintype "output"))
    )
    (net (code "74") (name "MOSI") (class "Default")
      (node (ref "IC14") (pin "1") (pinfunction "(PCINT8/~{OC1A}/SDA/DI/MOSI)PB0_1") (pintype "bidirectional"))
      (node (ref "J2") (pin "4") (pinfunction "4_4") (pintype "passive"))
    )
    (net (code "75") (name "NMI") (class "Default")
      (node (ref "IC18") (pin "21") (pinfunction "~{IRQB}_21") (pintype "output"))
      (node (ref "IC4") (pin "6") (pinfunction "NMIB_6") (pintype "input"))
      (node (ref "R8") (pin "2") (pinfunction "2_2") (pintype "passive"))
      (node (ref "S2") (pin "3") (pinfunction "P_3") (pintype "passive"))
      (node (ref "S2") (pin "4") (pinfunction "P1_4") (pintype "passive"))
      (node (ref "X1") (pin "B19") (pinfunction "P_B19") (pintype "passive"))
      (node (ref "X2") (pin "B19") (pinfunction "P_B19") (pintype "passive"))
      (node (ref "X3") (pin "B19") (pinfunction "P_B19") (pintype "passive"))
    )
    (net (code "76") (name "Net-(IC2A-CLR)") (class "Default")
      (node (ref "IC2") (pin "1") (pinfunction "CLR_1") (pintype "input"))
      (node (ref "IC2") (pin "4") (pinfunction "PRE_4") (pintype "input"))
      (node (ref "R3") (pin "2") (pinfunction "2_2") (pintype "passive"))
    )
    (net (code "77") (name "Net-(IC2A-D)") (class "Default")
      (node (ref "IC2") (pin "2") (pinfunction "D_2") (pintype "input"))
      (node (ref "IC2") (pin "6") (pinfunction "~{Q}_6") (pintype "output"))
    )
    (net (code "78") (name "Net-(IC2B-CLR)") (class "Default")
      (node (ref "IC2") (pin "10") (pinfunction "PRE_10") (pintype "input"))
      (node (ref "IC2") (pin "13") (pinfunction "CLR_13") (pintype "input"))
      (node (ref "R4") (pin "2") (pinfunction "2_2") (pintype "passive"))
    )
    (net (code "79") (name "Net-(IC2B-D)") (class "Default")
      (node (ref "IC2") (pin "12") (pinfunction "D_12") (pintype "input"))
      (node (ref "IC2") (pin "8") (pinfunction "~{Q}_8") (pintype "output"))
    )
    (net (code "80") (name "Net-(IC3A-CLR)") (class "Default")
      (node (ref "IC3") (pin "1") (pinfunction "CLR_1") (pintype "input"))
      (node (ref "IC3") (pin "4") (pinfunction "PRE_4") (pintype "input"))
      (node (ref "R5") (pin "2") (pinfunction "2_2") (pintype "passive"))
    )
    (net (code "81") (name "Net-(IC3A-D)") (class "Default")
      (node (ref "IC3") (pin "2") (pinfunction "D_2") (pintype "input"))
      (node (ref "IC3") (pin "6") (pinfunction "~{Q}_6") (pintype "output"))
    )
    (net (code "82") (name "Net-(IC3B-CLR)") (class "Default")
      (node (ref "IC3") (pin "10") (pinfunction "PRE_10") (pintype "input"))
      (node (ref "IC3") (pin "13") (pinfunction "CLR_13") (pintype "input"))
      (node (ref "R6") (pin "2") (pinfunction "2_2") (pintype "passive"))
    )
    (net (code "83") (name "Net-(IC3B-D)") (class "Default")
      (node (ref "IC3") (pin "12") (pinfunction "D_12") (pintype "input"))
      (node (ref "IC3") (pin "8") (pinfunction "~{Q}_8") (pintype "output"))
    )
    (net (code "84") (name "Net-(IC10A-O)") (class "Default")
      (node (ref "IC10") (pin "10") (pinfunction "I1_10") (pintype "input"))
      (node (ref "IC10") (pin "3") (pinfunction "O_3") (pintype "output"))
    )
    (net (code "85") (name "Net-(IC17A-A0)") (class "Default")
      (node (ref "IC17") (pin "9") (pinfunction "A0_9") (pintype "output"))
      (node (ref "IC27") (pin "3") (pinfunction "2D_3") (pintype "input"))
    )
    (net (code "86") (name "Net-(IC17A-A1)") (class "Default")
      (node (ref "IC17") (pin "7") (pinfunction "A1_7") (pintype "output"))
      (node (ref "IC27") (pin "4") (pinfunction "3D_4") (pintype "input"))
    )
    (net (code "87") (name "Net-(IC17A-A2)") (class "Default")
      (node (ref "IC17") (pin "6") (pinfunction "A2_6") (pintype "output"))
      (node (ref "IC27") (pin "5") (pinfunction "4D_5") (pintype "input"))
    )
    (net (code "88") (name "Net-(IC19-XTL1)") (class "Default")
      (node (ref "C29") (pin "2") (pinfunction "2_2") (pintype "passive"))
      (node (ref "IC19") (pin "6") (pinfunction "XTL1_6") (pintype "input"))
      (node (ref "Q1") (pin "1") (pinfunction "1_1") (pintype "passive"))
    )
    (net (code "89") (name "Net-(IC19-XTL2)") (class "Default")
      (node (ref "IC19") (pin "7") (pinfunction "XTL2_7") (pintype "output"))
      (node (ref "Q1") (pin "2") (pinfunction "2_2") (pintype "passive"))
    )
    (net (code "90") (name "Net-(LED1-PadA)") (class "Default")
      (node (ref "LED1") (pin "A") (pinfunction "A_A") (pintype "passive"))
      (node (ref "R1") (pin "1") (pinfunction "1_1") (pintype "passive"))
    )
    (net (code "91") (name "Net-(LED2-PadA)") (class "Default")
      (node (ref "LED2") (pin "A") (pinfunction "A_A") (pintype "passive"))
      (node (ref "R2") (pin "1") (pinfunction "1_1") (pintype "passive"))
    )
    (net (code "92") (name "Net-(LED3-PadA)") (class "Default")
      (node (ref "LED3") (pin "A") (pinfunction "A_A") (pintype "passive"))
      (node (ref "R10") (pin "1") (pinfunction "1_1") (pintype "passive"))
    )
    (net (code "93") (name "Net-(LED4-PadA)") (class "Default")
      (node (ref "LED4") (pin "A") (pinfunction "A_A") (pintype "passive"))
      (node (ref "R11") (pin "1") (pinfunction "1_1") (pintype "passive"))
    )
    (net (code "94") (name "Net-(LED5-PadA)") (class "Default")
      (node (ref "LED5") (pin "A") (pinfunction "A_A") (pintype "passive"))
      (node (ref "R12") (pin "1") (pinfunction "1_1") (pintype "passive"))
    )
    (net (code "95") (name "Net-(LED6-PadA)") (class "Default")
      (node (ref "LED6") (pin "A") (pinfunction "A_A") (pintype "passive"))
      (node (ref "R14") (pin "2") (pinfunction "2_2") (pintype "passive"))
    )
    (net (code "96") (name "Net-(LED7-PadA)") (class "Default")
      (node (ref "LED7") (pin "A") (pinfunction "A_A") (pintype "passive"))
      (node (ref "R15") (pin "2") (pinfunction "2_2") (pintype "passive"))
    )
    (net (code "97") (name "Net-(X1AG-P)") (class "Default")
      (node (ref "X1") (pin "B10") (pinfunction "P_B10") (pintype "passive"))
      (node (ref "X2") (pin "B10") (pinfunction "P_B10") (pintype "passive"))
      (node (ref "X3") (pin "B10") (pinfunction "P_B10") (pintype "passive"))
    )
    (net (code "98") (name "Net-(X1AJ-P)") (class "Default")
      (node (ref "X1") (pin "B13") (pinfunction "P_B13") (pintype "passive"))
      (node (ref "X2") (pin "B13") (pinfunction "P_B13") (pintype "passive"))
      (node (ref "X3") (pin "B13") (pinfunction "P_B13") (pintype "passive"))
    )
    (net (code "99") (name "Net-(X1AK-P)") (class "Default")
      (node (ref "X1") (pin "B14") (pinfunction "P_B14") (pintype "passive"))
      (node (ref "X2") (pin "B14") (pinfunction "P_B14") (pintype "passive"))
      (node (ref "X3") (pin "B14") (pinfunction "P_B14") (pintype "passive"))
    )
    (net (code "100") (name "Net-(X1AL-P)") (class "Default")
      (node (ref "X1") (pin "B15") (pinfunction "P_B15") (pintype "passive"))
      (node (ref "X2") (pin "B15") (pinfunction "P_B15") (pintype "passive"))
      (node (ref "X3") (pin "B15") (pinfunction "P_B15") (pintype "passive"))
    )
    (net (code "101") (name "Net-(X1AM-P)") (class "Default")
      (node (ref "X1") (pin "B16") (pinfunction "P_B16") (pintype "passive"))
      (node (ref "X2") (pin "B16") (pinfunction "P_B16") (pintype "passive"))
      (node (ref "X3") (pin "B16") (pinfunction "P_B16") (pintype "passive"))
    )
    (net (code "102") (name "Net-(X1AN-P)") (class "Default")
      (node (ref "X1") (pin "B17") (pinfunction "P_B17") (pintype "passive"))
      (node (ref "X2") (pin "B17") (pinfunction "P_B17") (pintype "passive"))
      (node (ref "X3") (pin "B17") (pinfunction "P_B17") (pintype "passive"))
    )
    (net (code "103") (name "Net-(X1AX-P)") (class "Default")
      (node (ref "X1") (pin "B26") (pinfunction "P_B26") (pintype "passive"))
      (node (ref "X2") (pin "B26") (pinfunction "P_B26") (pintype "passive"))
      (node (ref "X3") (pin "B26") (pinfunction "P_B26") (pintype "passive"))
    )
    (net (code "104") (name "Net-(X1AY-P)") (class "Default")
      (node (ref "X1") (pin "B27") (pinfunction "P_B27") (pintype "passive"))
      (node (ref "X2") (pin "B27") (pinfunction "P_B27") (pintype "passive"))
      (node (ref "X3") (pin "B27") (pinfunction "P_B27") (pintype "passive"))
    )
    (net (code "105") (name "Net-(X1BG-P)") (class "Default")
      (node (ref "X1") (pin "B6") (pinfunction "P_B6") (pintype "passive"))
      (node (ref "X2") (pin "B6") (pinfunction "P_B6") (pintype "passive"))
      (node (ref "X3") (pin "B6") (pinfunction "P_B6") (pintype "passive"))
    )
    (net (code "106") (name "Net-(X1BH-P)") (class "Default")
      (node (ref "X1") (pin "B7") (pinfunction "P_B7") (pintype "passive"))
      (node (ref "X2") (pin "B7") (pinfunction "P_B7") (pintype "passive"))
      (node (ref "X3") (pin "B7") (pinfunction "P_B7") (pintype "passive"))
    )
    (net (code "107") (name "Net-(X1BI-P)") (class "Default")
      (node (ref "X1") (pin "B8") (pinfunction "P_B8") (pintype "passive"))
      (node (ref "X2") (pin "B8") (pinfunction "P_B8") (pintype "passive"))
      (node (ref "X3") (pin "B8") (pinfunction "P_B8") (pintype "passive"))
    )
    (net (code "108") (name "Net-(X1BJ-P)") (class "Default")
      (node (ref "X1") (pin "B9") (pinfunction "P_B9") (pintype "passive"))
      (node (ref "X2") (pin "B9") (pinfunction "P_B9") (pintype "passive"))
      (node (ref "X3") (pin "B9") (pinfunction "P_B9") (pintype "passive"))
    )
    (net (code "109") (name "PA0") (class "Default")
      (node (ref "IC16") (pin "2") (pinfunction "PA0_2") (pintype "bidirectional"))
      (node (ref "JP8") (pin "3") (pinfunction "3_3") (pintype "passive"))
    )
    (net (code "110") (name "PA1") (class "Default")
      (node (ref "IC16") (pin "3") (pinfunction "PA1_3") (pintype "bidirectional"))
      (node (ref "JP8") (pin "5") (pinfunction "5_5") (pintype "passive"))
    )
    (net (code "111") (name "PA2") (class "Default")
      (node (ref "IC16") (pin "4") (pinfunction "PA2_4") (pintype "bidirectional"))
      (node (ref "JP8") (pin "7") (pinfunction "7_7") (pintype "passive"))
    )
    (net (code "112") (name "PA3") (class "Default")
      (node (ref "IC16") (pin "5") (pinfunction "PA3_5") (pintype "bidirectional"))
      (node (ref "JP8") (pin "9") (pinfunction "9_9") (pintype "passive"))
    )
    (net (code "113") (name "PA4") (class "Default")
      (node (ref "IC16") (pin "6") (pinfunction "PA4_6") (pintype "bidirectional"))
      (node (ref "JP8") (pin "11") (pinfunction "11_11") (pintype "passive"))
    )
    (net (code "114") (name "PA5") (class "Default")
      (node (ref "IC16") (pin "7") (pinfunction "PA5_7") (pintype "bidirectional"))
      (node (ref "JP8") (pin "13") (pinfunction "13_13") (pintype "passive"))
    )
    (net (code "115") (name "PA6") (class "Default")
      (node (ref "IC16") (pin "8") (pinfunction "PA6_8") (pintype "bidirectional"))
      (node (ref "JP8") (pin "15") (pinfunction "15_15") (pintype "passive"))
    )
    (net (code "116") (name "PA7") (class "Default")
      (node (ref "IC16") (pin "9") (pinfunction "PA7_9") (pintype "bidirectional"))
      (node (ref "JP8") (pin "17") (pinfunction "17_17") (pintype "passive"))
    )
    (net (code "117") (name "PB0") (class "Default")
      (node (ref "IC16") (pin "10") (pinfunction "PB0_10") (pintype "bidirectional"))
      (node (ref "JP8") (pin "4") (pinfunction "4_4") (pintype "passive"))
    )
    (net (code "118") (name "PB1") (class "Default")
      (node (ref "IC16") (pin "11") (pinfunction "PB1_11") (pintype "bidirectional"))
      (node (ref "JP8") (pin "6") (pinfunction "6_6") (pintype "passive"))
    )
    (net (code "119") (name "PB2") (class "Default")
      (node (ref "IC16") (pin "12") (pinfunction "PB2_12") (pintype "bidirectional"))
      (node (ref "JP8") (pin "8") (pinfunction "8_8") (pintype "passive"))
    )
    (net (code "120") (name "PB3") (class "Default")
      (node (ref "IC16") (pin "13") (pinfunction "PB3_13") (pintype "bidirectional"))
      (node (ref "JP8") (pin "10") (pinfunction "10_10") (pintype "passive"))
    )
    (net (code "121") (name "PB4") (class "Default")
      (node (ref "IC16") (pin "14") (pinfunction "PB4_14") (pintype "bidirectional"))
      (node (ref "JP8") (pin "12") (pinfunction "12_12") (pintype "passive"))
    )
    (net (code "122") (name "PB5") (class "Default")
      (node (ref "IC16") (pin "15") (pinfunction "PB5_15") (pintype "bidirectional"))
      (node (ref "JP8") (pin "14") (pinfunction "14_14") (pintype "passive"))
    )
    (net (code "123") (name "PB6") (class "Default")
      (node (ref "IC16") (pin "16") (pinfunction "PB6_16") (pintype "bidirectional"))
      (node (ref "JP8") (pin "16") (pinfunction "16_16") (pintype "passive"))
    )
    (net (code "124") (name "PB7") (class "Default")
      (node (ref "IC16") (pin "17") (pinfunction "PB7_17") (pintype "bidirectional"))
      (node (ref "JP8") (pin "18") (pinfunction "18_18") (pintype "passive"))
    )
    (net (code "125") (name "PHI2") (class "Default")
      (node (ref "IC10") (pin "13") (pinfunction "I1_13") (pintype "input"))
      (node (ref "IC10") (pin "9") (pinfunction "I0_9") (pintype "input"))
      (node (ref "IC16") (pin "25") (pinfunction "PHI2_25") (pintype "input"))
      (node (ref "IC18") (pin "25") (pinfunction "PHI2_25") (pintype "input"))
      (node (ref "IC19") (pin "27") (pinfunction "PHI2_27") (pintype "input"))
      (node (ref "IC27") (pin "11") (pinfunction "CLK_11") (pintype "input"))
      (node (ref "IC4") (pin "39") (pinfunction "PHI2_39") (pintype "output"))
      (node (ref "X1") (pin "B20") (pinfunction "P_B20") (pintype "passive"))
      (node (ref "X2") (pin "B20") (pinfunction "P_B20") (pintype "passive"))
      (node (ref "X3") (pin "B20") (pinfunction "P_B20") (pintype "passive"))
    )
    (net (code "126") (name "PS2_CLK") (class "Default")
      (node (ref "IC14") (pin "4") (pinfunction "(PCINT11/OC1B)PB3_4") (pintype "bidirectional"))
      (node (ref "X4") (pin "6") (pinfunction "6_6") (pintype "passive"))
    )
    (net (code "127") (name "PS2_DATA") (class "Default")
      (node (ref "IC14") (pin "7") (pinfunction "PB4(ADC7/XTAL1/PCINT12)_7") (pintype "bidirectional"))
      (node (ref "X4") (pin "1") (pinfunction "1_1") (pintype "passive"))
    )
    (net (code "128") (name "RDY") (class "Default")
      (node (ref "IC4") (pin "2") (pinfunction "RDY_2") (pintype "bidirectional"))
      (node (ref "R7") (pin "2") (pinfunction "2_2") (pintype "passive"))
    )
    (net (code "129") (name "RTS") (class "Default")
      (node (ref "IC19") (pin "8") (pinfunction "RTS_8") (pintype "output"))
      (node (ref "JP12") (pin "1") (pinfunction "1_1") (pintype "passive"))
    )
    (net (code "130") (name "RX") (class "Default")
      (node (ref "IC19") (pin "10") (pinfunction "TXD_10") (pintype "output"))
      (node (ref "JP11") (pin "2") (pinfunction "2_2") (pintype "passive"))
      (node (ref "U$1") (pin "5") (pinfunction "URX_5") (pintype "bidirectional"))
      (node (ref "X1") (pin "B4") (pinfunction "P_B4") (pintype "passive"))
      (node (ref "X2") (pin "B4") (pinfunction "P_B4") (pintype "passive"))
      (node (ref "X3") (pin "B4") (pinfunction "P_B4") (pintype "passive"))
    )
    (net (code "131") (name "R{slash}~{W}") (class "Default")
      (node (ref "IC10") (pin "1") (pinfunction "I0_1") (pintype "input"))
      (node (ref "IC10") (pin "12") (pinfunction "I0_12") (pintype "input"))
      (node (ref "IC10") (pin "2") (pinfunction "I1_2") (pintype "input"))
      (node (ref "IC16") (pin "22") (pinfunction "R~{WB}_22") (pintype "input"))
      (node (ref "IC18") (pin "22") (pinfunction "R~{WB}_22") (pintype "input"))
      (node (ref "IC19") (pin "28") (pinfunction "R/W_28") (pintype "input"))
      (node (ref "IC4") (pin "34") (pinfunction "R/WB_34") (pintype "output"))
      (node (ref "X1") (pin "A1") (pinfunction "P_A1") (pintype "passive"))
      (node (ref "X2") (pin "A1") (pinfunction "P_A1") (pintype "passive"))
      (node (ref "X3") (pin "A1") (pinfunction "P_A1") (pintype "passive"))
    )
    (net (code "132") (name "SCK") (class "Default")
      (node (ref "IC14") (pin "3") (pinfunction "(PCINT10/~{OC1B}/SCL/SCK)PB2_3") (pintype "bidirectional"))
      (node (ref "J2") (pin "3") (pinfunction "3_3") (pintype "passive"))
    )
    (net (code "133") (name "SYNC") (class "Default")
      (node (ref "IC4") (pin "7") (pinfunction "SYNC_7") (pintype "output"))
    )
    (net (code "134") (name "TX") (class "Default")
      (node (ref "IC19") (pin "12") (pinfunction "RXD_12") (pintype "input"))
      (node (ref "JP11") (pin "3") (pinfunction "3_3") (pintype "passive"))
      (node (ref "U$1") (pin "6") (pinfunction "UTX_6") (pintype "bidirectional"))
      (node (ref "X1") (pin "B5") (pinfunction "P_B5") (pintype "passive"))
      (node (ref "X2") (pin "B5") (pinfunction "P_B5") (pintype "passive"))
      (node (ref "X3") (pin "B5") (pinfunction "P_B5") (pintype "passive"))
    )
    (net (code "135") (name "VCC") (class "Default")
      (node (ref "J1") (pin "1") (pinfunction "1_1") (pintype "passive"))
      (node (ref "JP1") (pin "1") (pinfunction "1_1") (pintype "passive"))
    )
    (net (code "136") (name "VPB") (class "Default")
      (node (ref "IC4") (pin "1") (pinfunction "VPB_1") (pintype "output"))
    )
    (net (code "137") (name "unconnected-(IC4-NC-Pad35)") (class "Default")
      (node (ref "IC4") (pin "35") (pinfunction "NC_35") (pintype "no_connect"))
    )
    (net (code "138") (name "unconnected-(IC4-PHI1-Pad3)") (class "Default")
      (node (ref "IC4") (pin "3") (pinfunction "PHI1_3") (pintype "output"))
    )
    (net (code "139") (name "unconnected-(IC4-SOB-Pad38)") (class "Default")
      (node (ref "IC4") (pin "38") (pinfunction "SOB_38") (pintype "input"))
    )
    (net (code "140") (name "unconnected-(IC5-RDY{slash}~{BSY}-Pad1)") (class "Default")
      (node (ref "IC5") (pin "1") (pinfunction "RDY/~{BSY}_1") (pintype "output"))
    )
    (net (code "141") (name "unconnected-(IC11A-Y0-Pad4)") (class "Default")
      (node (ref "IC11") (pin "4") (pinfunction "Y0_4") (pintype "output"))
    )
    (net (code "142") (name "unconnected-(IC11A-Y1-Pad5)") (class "Default")
      (node (ref "IC11") (pin "5") (pinfunction "Y1_5") (pintype "output"))
    )
    (net (code "143") (name "unconnected-(IC11B-Y2-Pad10)") (class "Default")
      (node (ref "IC11") (pin "10") (pinfunction "Y2_10") (pintype "output"))
    )
    (net (code "144") (name "unconnected-(IC11B-Y3-Pad9)") (class "Default")
      (node (ref "IC11") (pin "9") (pinfunction "Y3_9") (pintype "output"))
    )
    (net (code "145") (name "unconnected-(IC17A-EO-Pad15)") (class "Default")
      (node (ref "IC17") (pin "15") (pinfunction "EO_15") (pintype "output"))
    )
    (net (code "146") (name "unconnected-(IC18A-CA1-Pad40)") (class "Default")
      (node (ref "IC18") (pin "40") (pinfunction "CA1_40") (pintype "bidirectional"))
    )
    (net (code "147") (name "unconnected-(IC18A-CA2-Pad39)") (class "Default")
      (node (ref "IC18") (pin "39") (pinfunction "CA2_39") (pintype "bidirectional"))
    )
    (net (code "148") (name "unconnected-(IC18A-CB1-Pad18)") (class "Default")
      (node (ref "IC18") (pin "18") (pinfunction "CB1_18") (pintype "bidirectional"))
    )
    (net (code "149") (name "unconnected-(IC18A-CB2-Pad19)") (class "Default")
      (node (ref "IC18") (pin "19") (pinfunction "CB2_19") (pintype "bidirectional"))
    )
    (net (code "150") (name "unconnected-(IC19-DTR-Pad11)") (class "Default")
      (node (ref "IC19") (pin "11") (pinfunction "DTR_11") (pintype "output"))
    )
    (net (code "151") (name "unconnected-(IC19-RXC-Pad5)") (class "Default")
      (node (ref "IC19") (pin "5") (pinfunction "RXC_5") (pintype "bidirectional"))
    )
    (net (code "152") (name "unconnected-(IC21D-I0-Pad12)") (class "Default")
      (node (ref "IC21") (pin "12") (pinfunction "I0_12") (pintype "input"))
    )
    (net (code "153") (name "unconnected-(IC21D-I1-Pad13)") (class "Default")
      (node (ref "IC21") (pin "13") (pinfunction "I1_13") (pintype "input"))
    )
    (net (code "154") (name "unconnected-(IC21D-O-Pad11)") (class "Default")
      (node (ref "IC21") (pin "11") (pinfunction "O_11") (pintype "output"))
    )
    (net (code "155") (name "unconnected-(J3-Pad5)") (class "Default")
      (node (ref "J3") (pin "5") (pinfunction "5_5") (pintype "passive"))
    )
    (net (code "156") (name "unconnected-(J3-Pad9)") (class "Default")
      (node (ref "J3") (pin "9") (pinfunction "9_9") (pintype "passive"))
    )
    (net (code "157") (name "unconnected-(J4-CC1-PadA5)") (class "Default")
      (node (ref "J4") (pin "A5") (pinfunction "CC1_A5") (pintype "bidirectional"))
    )
    (net (code "158") (name "unconnected-(J4-CC2-PadB5)") (class "Default")
      (node (ref "J4") (pin "B5") (pinfunction "CC2_B5") (pintype "bidirectional"))
    )
    (net (code "159") (name "unconnected-(JP6-Pad23)") (class "Default")
      (node (ref "JP6") (pin "23") (pinfunction "23_23") (pintype "passive"))
    )
    (net (code "160") (name "unconnected-(JP6-Pad24)") (class "Default")
      (node (ref "JP6") (pin "24") (pinfunction "24_24") (pintype "passive"))
    )
    (net (code "161") (name "unconnected-(JP11-Pad5)") (class "Default")
      (node (ref "JP11") (pin "5") (pinfunction "5_5") (pintype "passive"))
    )
    (net (code "162") (name "unconnected-(RN2-Pad2)") (class "Default")
      (node (ref "RN2") (pin "2") (pinfunction "2_2") (pintype "passive"))
    )
    (net (code "163") (name "unconnected-(RN2-Pad3)") (class "Default")
      (node (ref "RN2") (pin "3") (pinfunction "3_3") (pintype "passive"))
    )
    (net (code "164") (name "unconnected-(U$1-GP0-Pad2)") (class "Default")
      (node (ref "U$1") (pin "2") (pinfunction "GP0_2") (pintype "bidirectional"))
    )
    (net (code "165") (name "unconnected-(U$1-GP1-Pad3)") (class "Default")
      (node (ref "U$1") (pin "3") (pinfunction "GP1_3") (pintype "bidirectional"))
    )
    (net (code "166") (name "unconnected-(U$1-GP2-Pad7)") (class "Default")
      (node (ref "U$1") (pin "7") (pinfunction "GP2_7") (pintype "bidirectional"))
    )
    (net (code "167") (name "unconnected-(U$1-GP3-Pad8)") (class "Default")
      (node (ref "U$1") (pin "8") (pinfunction "GP3_8") (pintype "bidirectional"))
    )
    (net (code "168") (name "unconnected-(U$1-SCL-Pad10)") (class "Default")
      (node (ref "U$1") (pin "10") (pinfunction "SCL_10") (pintype "bidirectional"))
    )
    (net (code "169") (name "unconnected-(U$1-SDA-Pad9)") (class "Default")
      (node (ref "U$1") (pin "9") (pinfunction "SDA_9") (pintype "bidirectional"))
    )
    (net (code "170") (name "unconnected-(X4-Pad2)") (class "Default")
      (node (ref "X4") (pin "2") (pinfunction "2_2") (pintype "passive"))
    )
    (net (code "171") (name "unconnected-(X4-Pad8)") (class "Default")
      (node (ref "X4") (pin "8") (pinfunction "8_8") (pintype "passive"))
    )
    (net (code "172") (name "~{$C4-7}") (class "Default")
      (node (ref "IC21") (pin "4") (pinfunction "I0_4") (pintype "input"))
      (node (ref "IC21") (pin "9") (pinfunction "I0_9") (pintype "input"))
      (node (ref "IC9") (pin "5") (pinfunction "Y1_5") (pintype "output"))
    )
    (net (code "173") (name "~{$DXXX_CS}") (class "Default")
      (node (ref "IC11") (pin "11") (pinfunction "Y1_11") (pintype "output"))
      (node (ref "X1") (pin "B28") (pinfunction "P_B28") (pintype "passive"))
      (node (ref "X2") (pin "B28") (pinfunction "P_B28") (pintype "passive"))
      (node (ref "X3") (pin "B28") (pinfunction "P_B28") (pintype "passive"))
    )
    (net (code "174") (name "~{A7}") (class "Default")
      (node (ref "IC10") (pin "6") (pinfunction "O_6") (pintype "output"))
      (node (ref "IC18") (pin "24") (pinfunction "CS1_24") (pintype "input"))
      (node (ref "IC21") (pin "10") (pinfunction "I1_10") (pintype "input"))
    )
    (net (code "175") (name "~{AA_CS_WR}") (class "Default")
      (node (ref "IC21") (pin "3") (pinfunction "O_3") (pintype "output"))
    )
    (net (code "176") (name "~{AA_CS}") (class "Default")
      (node (ref "IC21") (pin "1") (pinfunction "I0_1") (pintype "input"))
      (node (ref "IC21") (pin "6") (pinfunction "O_6") (pintype "output"))
    )
    (net (code "177") (name "~{ACIA_CS}") (class "Default")
      (node (ref "IC19") (pin "3") (pinfunction "CS1_3") (pintype "input"))
      (node (ref "IC9") (pin "6") (pinfunction "Y2_6") (pintype "output"))
    )
    (net (code "178") (name "~{C-F}") (class "Default")
      (node (ref "IC11") (pin "15") (pinfunction "G_15") (pintype "input"))
      (node (ref "IC11") (pin "7") (pinfunction "Y3_7") (pintype "output"))
      (node (ref "IC12") (pin "1") (pinfunction "I0_1") (pintype "input"))
      (node (ref "IC12") (pin "2") (pinfunction "I1_2") (pintype "input"))
    )
    (net (code "179") (name "~{DEV0_CS}") (class "Default")
      (node (ref "IC9") (pin "11") (pinfunction "Y1_11") (pintype "output"))
      (node (ref "X1") (pin "A14") (pinfunction "P_A14") (pintype "passive"))
      (node (ref "X2") (pin "A14") (pinfunction "P_A14") (pintype "passive"))
      (node (ref "X3") (pin "A14") (pinfunction "P_A14") (pintype "passive"))
    )
    (net (code "180") (name "~{DEV1_CS}") (class "Default")
      (node (ref "IC9") (pin "10") (pinfunction "Y2_10") (pintype "output"))
      (node (ref "X1") (pin "A13") (pinfunction "P_A13") (pintype "passive"))
      (node (ref "X2") (pin "A13") (pinfunction "P_A13") (pintype "passive"))
      (node (ref "X3") (pin "A13") (pinfunction "P_A13") (pintype "passive"))
    )
    (net (code "181") (name "~{DEV2_CS}") (class "Default")
      (node (ref "IC9") (pin "9") (pinfunction "Y3_9") (pintype "output"))
      (node (ref "X1") (pin "A12") (pinfunction "P_A12") (pintype "passive"))
      (node (ref "X2") (pin "A12") (pinfunction "P_A12") (pintype "passive"))
      (node (ref "X3") (pin "A12") (pinfunction "P_A12") (pintype "passive"))
    )
    (net (code "182") (name "~{E-F}") (class "Default")
      (node (ref "IC12") (pin "10") (pinfunction "I1_10") (pintype "input"))
      (node (ref "IC12") (pin "6") (pinfunction "O_6") (pintype "output"))
      (node (ref "IC12") (pin "9") (pinfunction "I0_9") (pintype "input"))
    )
    (net (code "183") (name "~{EXROM}") (class "Default")
      (node (ref "IC12") (pin "13") (pinfunction "I1_13") (pintype "input"))
      (node (ref "R16") (pin "1") (pinfunction "1_1") (pintype "passive"))
      (node (ref "X1") (pin "A15") (pinfunction "P_A15") (pintype "passive"))
      (node (ref "X2") (pin "A15") (pinfunction "P_A15") (pintype "passive"))
      (node (ref "X3") (pin "A15") (pinfunction "P_A15") (pintype "passive"))
    )
    (net (code "184") (name "~{HRAM_CS}") (class "Default")
      (node (ref "IC11") (pin "6") (pinfunction "Y2_6") (pintype "output"))
      (node (ref "IC7") (pin "20") (pinfunction "~{CS}_20") (pintype "input"))
    )
    (net (code "185") (name "~{IO_CS}") (class "Default")
      (node (ref "IC11") (pin "12") (pinfunction "Y0_12") (pintype "output"))
      (node (ref "IC9") (pin "1") (pinfunction "G_1") (pintype "input"))
      (node (ref "LED4") (pin "K") (pinfunction "C_K") (pintype "passive"))
      (node (ref "X1") (pin "A10") (pinfunction "P_A10") (pintype "passive"))
      (node (ref "X2") (pin "A10") (pinfunction "P_A10") (pintype "passive"))
      (node (ref "X3") (pin "A10") (pinfunction "P_A10") (pintype "passive"))
    )
    (net (code "186") (name "~{IRQ_CS}") (class "Default")
      (node (ref "IC21") (pin "8") (pinfunction "O_8") (pintype "output"))
      (node (ref "IC27") (pin "1") (pinfunction "OC_1") (pintype "input"))
    )
    (net (code "187") (name "~{MEMR}") (class "Default")
      (node (ref "IC10") (pin "11") (pinfunction "O_11") (pintype "output"))
      (node (ref "IC5") (pin "22") (pinfunction "~{OE}_22") (pintype "input"))
      (node (ref "IC6") (pin "22") (pinfunction "~{OE}_22") (pintype "input"))
      (node (ref "IC7") (pin "22") (pinfunction "~{OE}_22") (pintype "input"))
      (node (ref "JP6") (pin "16") (pinfunction "16_16") (pintype "passive"))
      (node (ref "LED6") (pin "K") (pinfunction "C_K") (pintype "passive"))
      (node (ref "X1") (pin "B12") (pinfunction "P_B12") (pintype "passive"))
      (node (ref "X2") (pin "B12") (pinfunction "P_B12") (pintype "passive"))
      (node (ref "X3") (pin "B12") (pinfunction "P_B12") (pintype "passive"))
    )
    (net (code "188") (name "~{MEMW}") (class "Default")
      (node (ref "IC10") (pin "8") (pinfunction "O_8") (pintype "output"))
      (node (ref "IC21") (pin "2") (pinfunction "I1_2") (pintype "input"))
      (node (ref "IC6") (pin "27") (pinfunction "~{WE}_27") (pintype "input"))
      (node (ref "IC7") (pin "27") (pinfunction "~{WE}_27") (pintype "input"))
      (node (ref "JP6") (pin "13") (pinfunction "13_13") (pintype "passive"))
      (node (ref "LED7") (pin "K") (pinfunction "C_K") (pintype "passive"))
      (node (ref "X1") (pin "B11") (pinfunction "P_B11") (pintype "passive"))
      (node (ref "X2") (pin "B11") (pinfunction "P_B11") (pintype "passive"))
      (node (ref "X3") (pin "B11") (pinfunction "P_B11") (pintype "passive"))
    )
    (net (code "189") (name "~{OTHER_CS}") (class "Default")
      (node (ref "IC9") (pin "15") (pinfunction "G_15") (pintype "input"))
      (node (ref "IC9") (pin "7") (pinfunction "Y3_7") (pintype "output"))
    )
    (net (code "190") (name "~{RESET}") (class "Default")
      (node (ref "IC16") (pin "34") (pinfunction "~{RESB}_34") (pintype "input"))
      (node (ref "IC18") (pin "34") (pinfunction "~{RESB}_34") (pintype "input"))
      (node (ref "IC19") (pin "4") (pinfunction "RES_4") (pintype "input"))
      (node (ref "IC4") (pin "40") (pinfunction "RESB_40") (pintype "input"))
      (node (ref "IC8") (pin "1") (pinfunction "~{RESET}_1") (pintype "bidirectional"))
      (node (ref "JP6") (pin "12") (pinfunction "12_12") (pintype "passive"))
      (node (ref "LED5") (pin "K") (pinfunction "C_K") (pintype "passive"))
      (node (ref "R13") (pin "2") (pinfunction "2_2") (pintype "passive"))
      (node (ref "S3") (pin "3") (pinfunction "P_3") (pintype "passive"))
      (node (ref "S3") (pin "4") (pinfunction "P1_4") (pintype "passive"))
      (node (ref "SJ1") (pin "1") (pinfunction "1_1") (pintype "passive"))
      (node (ref "SJ3") (pin "1") (pinfunction "1_1") (pintype "passive"))
      (node (ref "SJ4") (pin "2") (pinfunction "2_2") (pintype "passive"))
      (node (ref "X1") (pin "B2") (pinfunction "P_B2") (pintype "passive"))
      (node (ref "X2") (pin "B2") (pinfunction "P_B2") (pintype "passive"))
      (node (ref "X3") (pin "B2") (pinfunction "P_B2") (pintype "passive"))
    )
    (net (code "191") (name "~{ROM_CS}") (class "Default")
      (node (ref "IC12") (pin "11") (pinfunction "O_11") (pintype "output"))
      (node (ref "IC5") (pin "20") (pinfunction "~{CE}_20") (pintype "input"))
    )
    (net (code "192") (name "~{USB_RESET}") (class "Default")
      (node (ref "SJ4") (pin "1") (pinfunction "1_1") (pintype "passive"))
      (node (ref "U$1") (pin "4") (pinfunction "~{RST}_4") (pintype "bidirectional"))
    )
    (net (code "193") (name "~{VERA_CS}") (class "Default")
      (node (ref "IC9") (pin "4") (pinfunction "Y0_4") (pintype "output"))
      (node (ref "JP6") (pin "11") (pinfunction "11_11") (pintype "passive"))
    )
    (net (code "194") (name "~{VIA_CS}") (class "Default")
      (node (ref "IC16") (pin "23") (pinfunction "~{CS2B}_23") (pintype "input"))
      (node (ref "IC18") (pin "23") (pinfunction "~{CS2B}_23") (pintype "input"))
      (node (ref "IC9") (pin "12") (pinfunction "Y0_12") (pintype "output"))
    )
  )
)
